# GameBit_Board.net
KiCad netlist of a schematic drawn in EAGLE
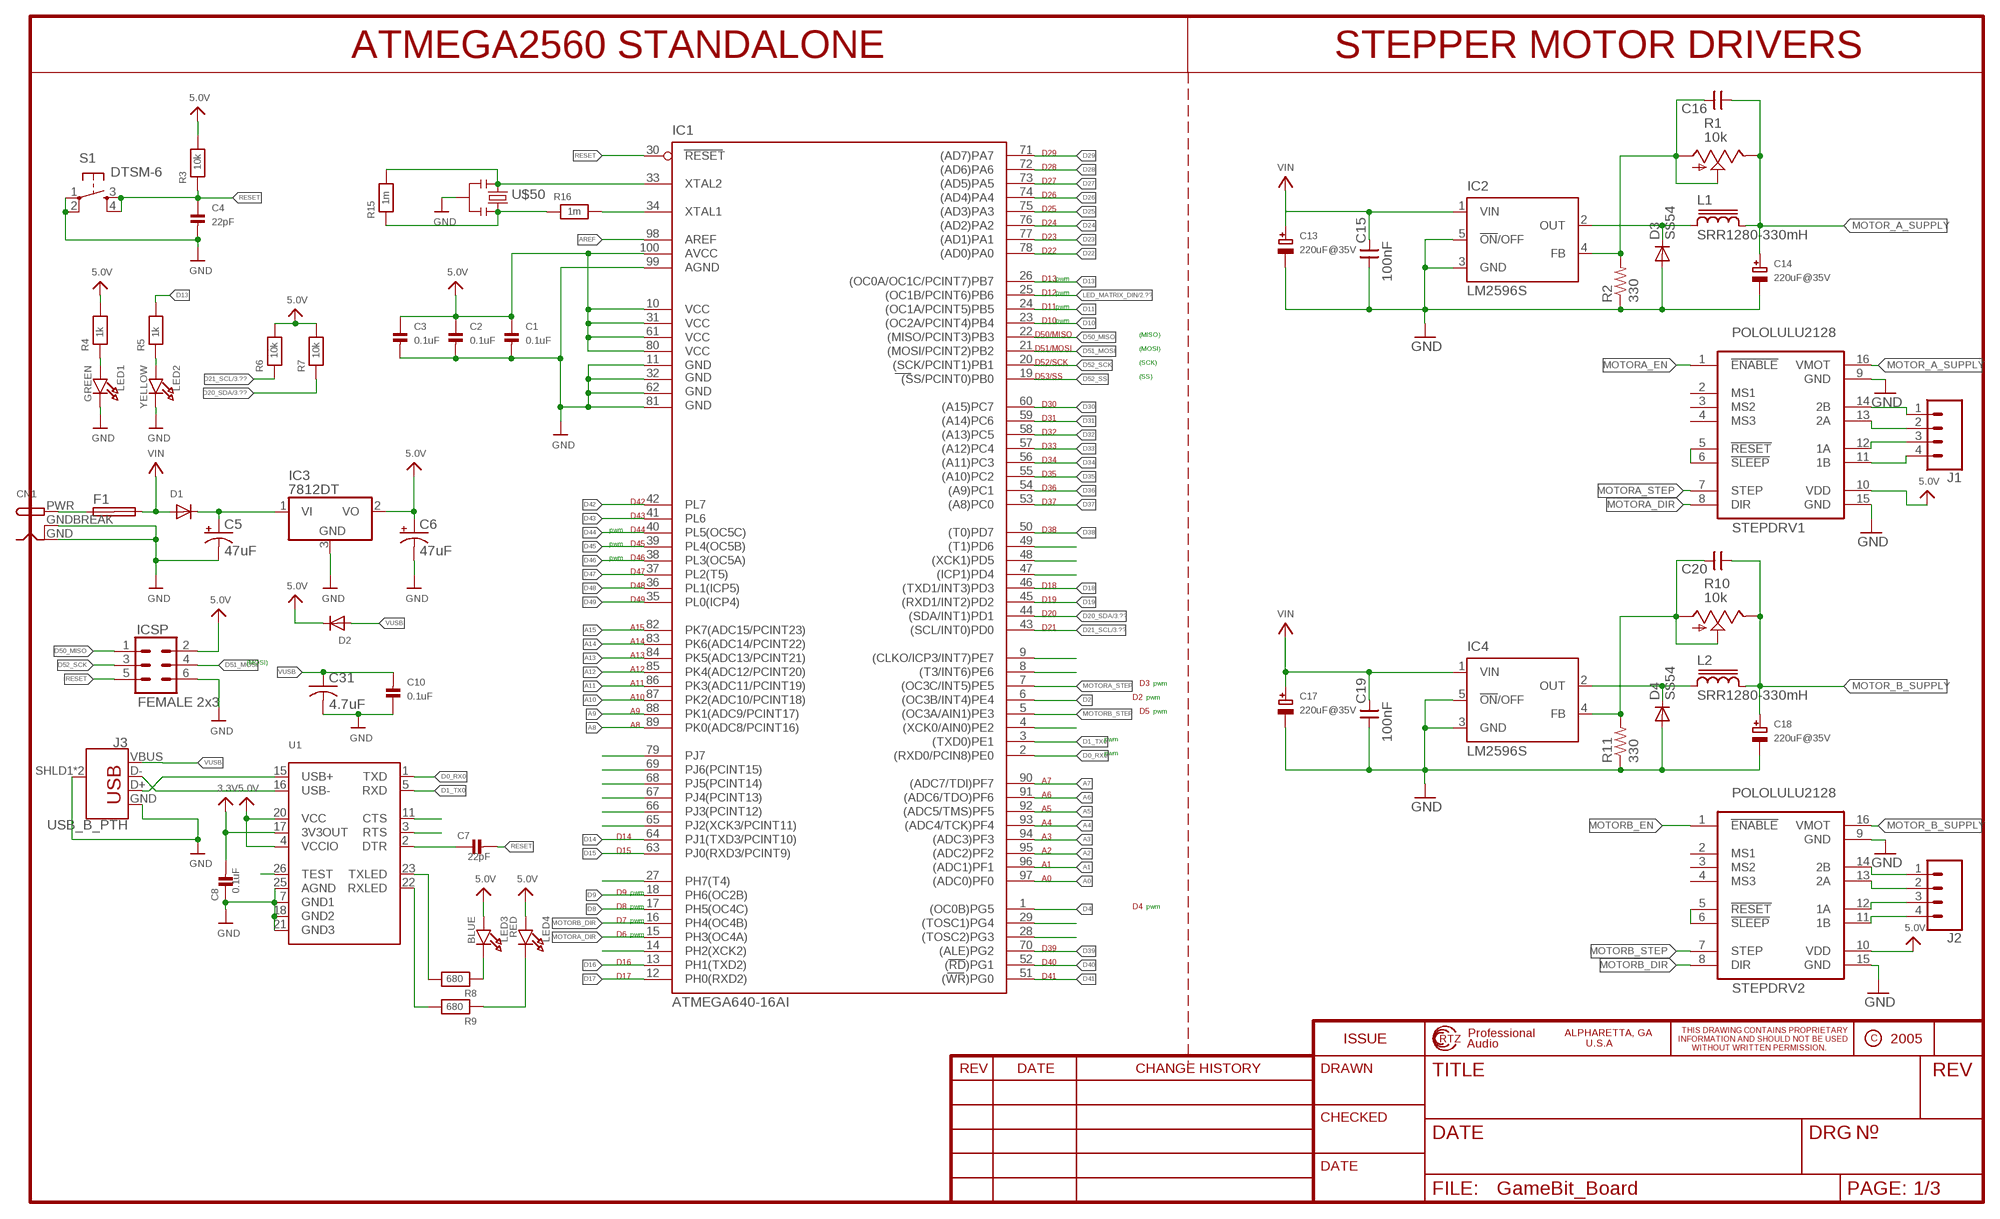
[diagram p0: schematic, sheet 1]
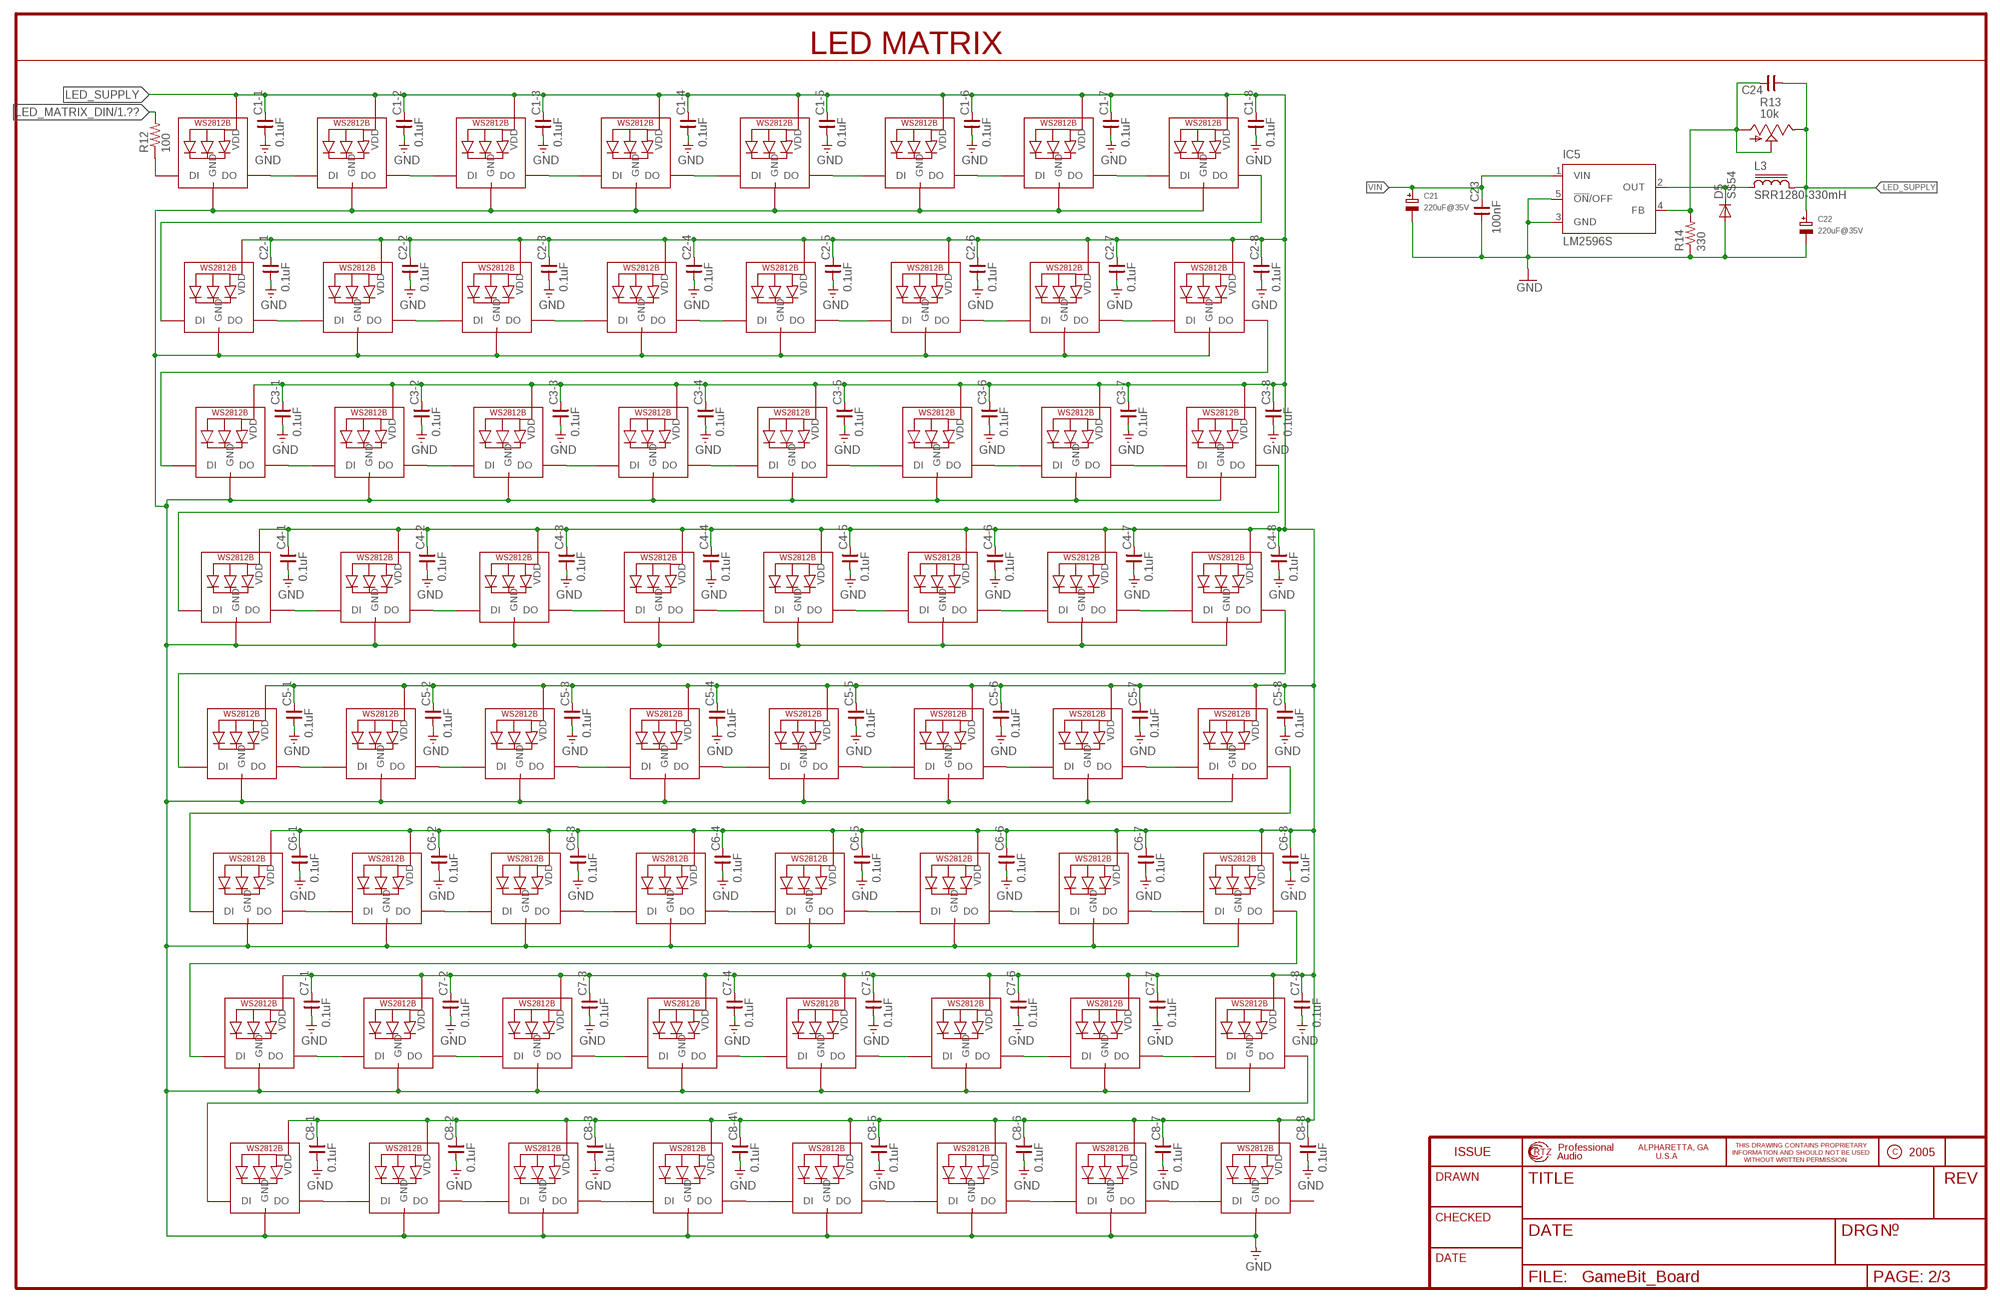
[diagram p1: schematic, sheet 2]
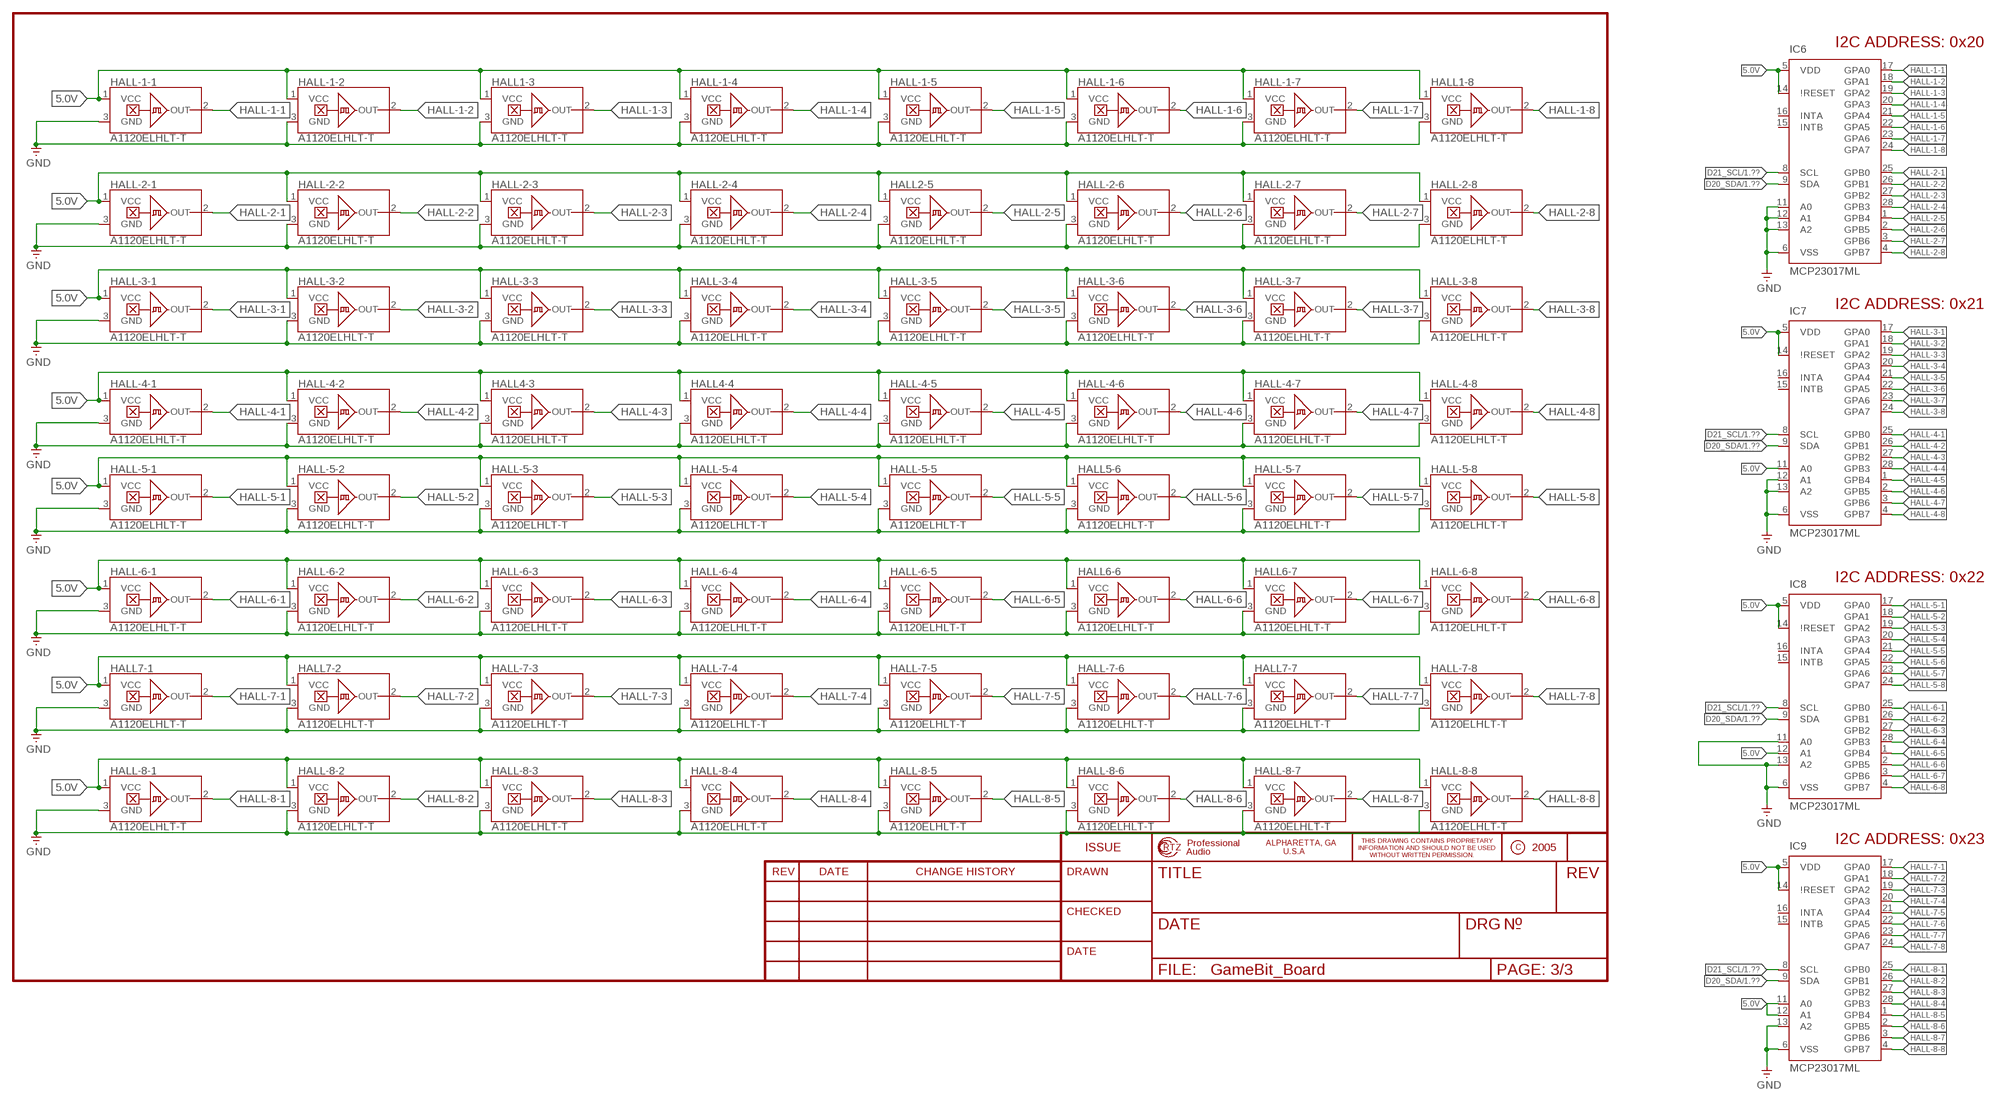
[diagram p2: schematic, sheet 3]

(export (version "E")
  (design (tool "Eeschema 10.0.6"))
  (components
    (comp (ref "C1")
      (value "0.1uF")
      (footprint "eagle-import:0603")
      (libsource (lib "eagle-import") (part "CAP_CERAMIC0603"))
    )
    (comp (ref "C2")
      (value "0.1uF")
      (footprint "eagle-import:0603")
      (libsource (lib "eagle-import") (part "CAP_CERAMIC0603"))
    )
    (comp (ref "C3")
      (value "0.1uF")
      (footprint "eagle-import:0603")
      (libsource (lib "eagle-import") (part "CAP_CERAMIC0603"))
    )
    (comp (ref "C4")
      (value "22pF")
      (footprint "eagle-import:0603")
      (libsource (lib "eagle-import") (part "CAP_CERAMIC0603"))
    )
    (comp (ref "C5")
      (value "47uF")
      (footprint "eagle-import:PANASONIC_D")
      (libsource (lib "eagle-import") (part "CPOL-USD"))
    )
    (comp (ref "C6")
      (value "47uF")
      (footprint "eagle-import:PANASONIC_D")
      (libsource (lib "eagle-import") (part "CPOL-USD"))
    )
    (comp (ref "C7")
      (value "22pF")
      (footprint "eagle-import:0603")
      (libsource (lib "eagle-import") (part "CAP_CERAMIC0603"))
    )
    (comp (ref "C8")
      (value "0.1uF")
      (footprint "eagle-import:0603")
      (libsource (lib "eagle-import") (part "CAP_CERAMIC0603"))
    )
    (comp (ref "C10")
      (value "0.1uF")
      (footprint "eagle-import:0603")
      (libsource (lib "eagle-import") (part "CAP_CERAMIC0603"))
    )
    (comp (ref "C13")
      (value "220uF@35V")
      (footprint "eagle-import:PANASONIC_D")
      (libsource (lib "eagle-import") (part "CAP_ELECTROLYTICPANASONIC_D"))
    )
    (comp (ref "C14")
      (value "220uF@35V")
      (footprint "eagle-import:PANASONIC_D")
      (libsource (lib "eagle-import") (part "CAP_ELECTROLYTICPANASONIC_D"))
    )
    (comp (ref "C15")
      (value "100nF")
      (footprint "eagle-import:0603")
      (libsource (lib "eagle-import") (part "CNP-0603"))
    )
    (comp (ref "C16")
      (value "CNP-0603")
      (footprint "eagle-import:0603")
      (libsource (lib "eagle-import") (part "CNP-0603"))
    )
    (comp (ref "C17")
      (value "220uF@35V")
      (footprint "eagle-import:PANASONIC_D")
      (libsource (lib "eagle-import") (part "CAP_ELECTROLYTICPANASONIC_D"))
    )
    (comp (ref "C18")
      (value "220uF@35V")
      (footprint "eagle-import:PANASONIC_D")
      (libsource (lib "eagle-import") (part "CAP_ELECTROLYTICPANASONIC_D"))
    )
    (comp (ref "C19")
      (value "100nF")
      (footprint "eagle-import:0603")
      (libsource (lib "eagle-import") (part "CNP-0603"))
    )
    (comp (ref "C20")
      (value "CNP-0603")
      (footprint "eagle-import:0603")
      (libsource (lib "eagle-import") (part "CNP-0603"))
    )
    (comp (ref "C31")
      (value "4.7uF")
      (footprint "eagle-import:C0805")
      (libsource (lib "eagle-import") (part "C-USC0805"))
    )
    (comp (ref "CN1")
      (value "DCBARRELPTH")
      (footprint "eagle-import:DCJACK_2MM_PTH")
      (libsource (lib "eagle-import") (part "DCBARRELPTH"))
    )
    (comp (ref "D1")
      (value "DIODESOD-123")
      (footprint "eagle-import:SOD-123")
      (libsource (lib "eagle-import") (part "DIODESOD-123"))
    )
    (comp (ref "D2")
      (value "DIODESOD-123")
      (footprint "eagle-import:SOD-123")
      (libsource (lib "eagle-import") (part "DIODESOD-123"))
    )
    (comp (ref "D3")
      (value "SS54")
      (footprint "eagle-import:DO214AB")
      (fields (field (name "MF") "Fairchild") (field (name "MPN") "S3G"))
      (libsource (lib "eagle-import") (part "S3G"))
    )
    (comp (ref "D4")
      (value "SS54")
      (footprint "eagle-import:DO214AB")
      (fields (field (name "MF") "Fairchild") (field (name "MPN") "S3G"))
      (libsource (lib "eagle-import") (part "S3G"))
    )
    (comp (ref "F1")
      (value "SHK20L")
      (footprint "eagle-import:SHK20L")
      (libsource (lib "eagle-import") (part "SHK20L"))
    )
    (comp (ref "IC1")
      (value "ATMEGA640-16AI")
      (footprint "eagle-import:TQFP100")
      (libsource (lib "eagle-import") (part "ATMEGAAI640-16"))
    )
    (comp (ref "IC2")
      (value "LM2596S")
      (footprint "eagle-import:TO263-5")
      (fields (field (name "MF") "NATIONAL SEMICONDUCTOR") (field (name "MPN") "LM2596S-ADJ/NOPB"))
      (libsource (lib "eagle-import") (part "LM2596S"))
    )
    (comp (ref "IC3")
      (value "7812DT")
      (footprint "eagle-import:TO252")
      (libsource (lib "eagle-import") (part "78DT12"))
    )
    (comp (ref "IC4")
      (value "LM2596S")
      (footprint "eagle-import:TO263-5")
      (fields (field (name "MF") "NATIONAL SEMICONDUCTOR") (field (name "MPN") "LM2596S-ADJ/NOPB"))
      (libsource (lib "eagle-import") (part "LM2596S"))
    )
    (comp (ref "ICSP")
      (value "FEMALE 2x3")
      (footprint "eagle-import:2X3")
      (libsource (lib "eagle-import") (part "CONN_03X2FEMALE"))
    )
    (comp (ref "J1")
      (value "CONN_04JST-PTH-VERT")
      (footprint "eagle-import:JST-4-PTH-VERT")
      (libsource (lib "eagle-import") (part "CONN_04JST-PTH-VERT"))
    )
    (comp (ref "J2")
      (value "CONN_04JST-PTH-VERT")
      (footprint "eagle-import:JST-4-PTH-VERT")
      (libsource (lib "eagle-import") (part "CONN_04JST-PTH-VERT"))
    )
    (comp (ref "J3")
      (value "USB_B_PTH")
      (footprint "eagle-import:USB-B-PTH")
      (libsource (lib "eagle-import") (part "USB_B_PTH"))
    )
    (comp (ref "L1")
      (value "SRR1280-330mH")
      (footprint "eagle-import:SRR1280")
      (libsource (lib "eagle-import") (part "SRR1280"))
    )
    (comp (ref "L2")
      (value "SRR1280-330mH")
      (footprint "eagle-import:SRR1280")
      (libsource (lib "eagle-import") (part "SRR1280"))
    )
    (comp (ref "LED1")
      (value "GREEN")
      (footprint "eagle-import:CHIPLED_0603")
      (libsource (lib "eagle-import") (part "LED0603"))
    )
    (comp (ref "LED2")
      (value "YELLOW")
      (footprint "eagle-import:CHIPLED_0603")
      (libsource (lib "eagle-import") (part "LED0603"))
    )
    (comp (ref "LED3")
      (value "BLUE")
      (footprint "eagle-import:CHIPLED_0603")
      (libsource (lib "eagle-import") (part "LED0603"))
    )
    (comp (ref "LED4")
      (value "RED")
      (footprint "eagle-import:CHIPLED_0603")
      (libsource (lib "eagle-import") (part "LED0603"))
    )
    (comp (ref "R1")
      (value "10k")
      (footprint "eagle-import:S64W")
      (libsource (lib "eagle-import") (part "TRIM_US-S64W"))
    )
    (comp (ref "R2")
      (value "330")
      (footprint "eagle-import:R0603")
      (libsource (lib "eagle-import") (part "R-US_R0603"))
    )
    (comp (ref "R3")
      (value "10k")
      (footprint "eagle-import:0603")
      (libsource (lib "eagle-import") (part "RESISTOR0603"))
    )
    (comp (ref "R4")
      (value "1k")
      (footprint "eagle-import:0603")
      (libsource (lib "eagle-import") (part "RESISTOR0603"))
    )
    (comp (ref "R5")
      (value "1k")
      (footprint "eagle-import:0603")
      (libsource (lib "eagle-import") (part "RESISTOR0603"))
    )
    (comp (ref "R6")
      (value "10k")
      (footprint "eagle-import:0603")
      (libsource (lib "eagle-import") (part "RESISTOR0603"))
    )
    (comp (ref "R7")
      (value "10k")
      (footprint "eagle-import:0603")
      (libsource (lib "eagle-import") (part "RESISTOR0603"))
    )
    (comp (ref "R8")
      (value "680")
      (footprint "eagle-import:0603")
      (libsource (lib "eagle-import") (part "RESISTOR0603"))
    )
    (comp (ref "R9")
      (value "680")
      (footprint "eagle-import:0603")
      (libsource (lib "eagle-import") (part "RESISTOR0603"))
    )
    (comp (ref "R10")
      (value "10k")
      (footprint "eagle-import:S64W")
      (libsource (lib "eagle-import") (part "TRIM_US-S64W"))
    )
    (comp (ref "R11")
      (value "330")
      (footprint "eagle-import:R0603")
      (libsource (lib "eagle-import") (part "R-US_R0603"))
    )
    (comp (ref "R15")
      (value "1m")
      (footprint "eagle-import:0805")
      (libsource (lib "eagle-import") (part "RESISTOR0805"))
    )
    (comp (ref "R16")
      (value "1m")
      (footprint "eagle-import:0805")
      (libsource (lib "eagle-import") (part "RESISTOR0805"))
    )
    (comp (ref "S1")
      (value "DTSM-6")
      (footprint "eagle-import:DTSM-6")
      (libsource (lib "eagle-import") (part "DTSM-6"))
    )
    (comp (ref "STEPDRV1")
      (value "POLOLULU2128")
      (footprint "eagle-import:POLOLULU2128")
      (libsource (lib "eagle-import") (part "POLOLULU2128"))
    )
    (comp (ref "STEPDRV2")
      (value "POLOLULU2128")
      (footprint "eagle-import:POLOLULU2128")
      (libsource (lib "eagle-import") (part "POLOLULU2128"))
    )
    (comp (ref "U$50")
      (value "RESONATORSMD")
      (footprint "eagle-import:RESONATOR-SMD")
      (libsource (lib "eagle-import") (part "RESONATORSMD"))
    )
    (comp (ref "U1")
      (value "FT232RLSSOP28")
      (footprint "eagle-import:SSOP28DB")
      (libsource (lib "eagle-import") (part "FT232RLSSOP28"))
    )
    (comp (ref "C1-1")
      (value "0.1uF")
      (footprint "eagle-import:0805")
      (libsource (lib "eagle-import") (part "CNP-0805"))
    )
    (comp (ref "C1-2")
      (value "0.1uF")
      (footprint "eagle-import:0805")
      (libsource (lib "eagle-import") (part "CNP-0805"))
    )
    (comp (ref "C1-3")
      (value "0.1uF")
      (footprint "eagle-import:0805")
      (libsource (lib "eagle-import") (part "CNP-0805"))
    )
    (comp (ref "C1-4")
      (value "0.1uF")
      (footprint "eagle-import:0805")
      (libsource (lib "eagle-import") (part "CNP-0805"))
    )
    (comp (ref "C1-5")
      (value "0.1uF")
      (footprint "eagle-import:0805")
      (libsource (lib "eagle-import") (part "CNP-0805"))
    )
    (comp (ref "C1-6")
      (value "0.1uF")
      (footprint "eagle-import:0805")
      (libsource (lib "eagle-import") (part "CNP-0805"))
    )
    (comp (ref "C1-7")
      (value "0.1uF")
      (footprint "eagle-import:0805")
      (libsource (lib "eagle-import") (part "CNP-0805"))
    )
    (comp (ref "C1-8")
      (value "0.1uF")
      (footprint "eagle-import:0805")
      (libsource (lib "eagle-import") (part "CNP-0805"))
    )
    (comp (ref "C2-1")
      (value "0.1uF")
      (footprint "eagle-import:0805")
      (libsource (lib "eagle-import") (part "CNP-0805"))
    )
    (comp (ref "C2-2")
      (value "0.1uF")
      (footprint "eagle-import:0805")
      (libsource (lib "eagle-import") (part "CNP-0805"))
    )
    (comp (ref "C2-3")
      (value "0.1uF")
      (footprint "eagle-import:0805")
      (libsource (lib "eagle-import") (part "CNP-0805"))
    )
    (comp (ref "C2-4")
      (value "0.1uF")
      (footprint "eagle-import:0805")
      (libsource (lib "eagle-import") (part "CNP-0805"))
    )
    (comp (ref "C2-5")
      (value "0.1uF")
      (footprint "eagle-import:0805")
      (libsource (lib "eagle-import") (part "CNP-0805"))
    )
    (comp (ref "C2-6")
      (value "0.1uF")
      (footprint "eagle-import:0805")
      (libsource (lib "eagle-import") (part "CNP-0805"))
    )
    (comp (ref "C2-7")
      (value "0.1uF")
      (footprint "eagle-import:0805")
      (libsource (lib "eagle-import") (part "CNP-0805"))
    )
    (comp (ref "C2-8")
      (value "0.1uF")
      (footprint "eagle-import:0805")
      (libsource (lib "eagle-import") (part "CNP-0805"))
    )
    (comp (ref "C3-1")
      (value "0.1uF")
      (footprint "eagle-import:0805")
      (libsource (lib "eagle-import") (part "CNP-0805"))
    )
    (comp (ref "C3-2")
      (value "0.1uF")
      (footprint "eagle-import:0805")
      (libsource (lib "eagle-import") (part "CNP-0805"))
    )
    (comp (ref "C3-3")
      (value "0.1uF")
      (footprint "eagle-import:0805")
      (libsource (lib "eagle-import") (part "CNP-0805"))
    )
    (comp (ref "C3-4")
      (value "0.1uF")
      (footprint "eagle-import:0805")
      (libsource (lib "eagle-import") (part "CNP-0805"))
    )
    (comp (ref "C3-5")
      (value "0.1uF")
      (footprint "eagle-import:0805")
      (libsource (lib "eagle-import") (part "CNP-0805"))
    )
    (comp (ref "C3-6")
      (value "0.1uF")
      (footprint "eagle-import:0805")
      (libsource (lib "eagle-import") (part "CNP-0805"))
    )
    (comp (ref "C3-7")
      (value "0.1uF")
      (footprint "eagle-import:0805")
      (libsource (lib "eagle-import") (part "CNP-0805"))
    )
    (comp (ref "C3-8")
      (value "0.1uF")
      (footprint "eagle-import:0805")
      (libsource (lib "eagle-import") (part "CNP-0805"))
    )
    (comp (ref "C4-1")
      (value "0.1uF")
      (footprint "eagle-import:0805")
      (libsource (lib "eagle-import") (part "CNP-0805"))
    )
    (comp (ref "C4-2")
      (value "0.1uF")
      (footprint "eagle-import:0805")
      (libsource (lib "eagle-import") (part "CNP-0805"))
    )
    (comp (ref "C4-3")
      (value "0.1uF")
      (footprint "eagle-import:0805")
      (libsource (lib "eagle-import") (part "CNP-0805"))
    )
    (comp (ref "C4-4")
      (value "0.1uF")
      (footprint "eagle-import:0805")
      (libsource (lib "eagle-import") (part "CNP-0805"))
    )
    (comp (ref "C4-5")
      (value "0.1uF")
      (footprint "eagle-import:0805")
      (libsource (lib "eagle-import") (part "CNP-0805"))
    )
    (comp (ref "C4-6")
      (value "0.1uF")
      (footprint "eagle-import:0805")
      (libsource (lib "eagle-import") (part "CNP-0805"))
    )
    (comp (ref "C4-7")
      (value "0.1uF")
      (footprint "eagle-import:0805")
      (libsource (lib "eagle-import") (part "CNP-0805"))
    )
    (comp (ref "C4-8")
      (value "0.1uF")
      (footprint "eagle-import:0805")
      (libsource (lib "eagle-import") (part "CNP-0805"))
    )
    (comp (ref "C5-1")
      (value "0.1uF")
      (footprint "eagle-import:0805")
      (libsource (lib "eagle-import") (part "CNP-0805"))
    )
    (comp (ref "C5-2")
      (value "0.1uF")
      (footprint "eagle-import:0805")
      (libsource (lib "eagle-import") (part "CNP-0805"))
    )
    (comp (ref "C5-3")
      (value "0.1uF")
      (footprint "eagle-import:0805")
      (libsource (lib "eagle-import") (part "CNP-0805"))
    )
    (comp (ref "C5-4")
      (value "0.1uF")
      (footprint "eagle-import:0805")
      (libsource (lib "eagle-import") (part "CNP-0805"))
    )
    (comp (ref "C5-5")
      (value "0.1uF")
      (footprint "eagle-import:0805")
      (libsource (lib "eagle-import") (part "CNP-0805"))
    )
    (comp (ref "C5-6")
      (value "0.1uF")
      (footprint "eagle-import:0805")
      (libsource (lib "eagle-import") (part "CNP-0805"))
    )
    (comp (ref "C5-7")
      (value "0.1uF")
      (footprint "eagle-import:0805")
      (libsource (lib "eagle-import") (part "CNP-0805"))
    )
    (comp (ref "C5-8")
      (value "0.1uF")
      (footprint "eagle-import:0805")
      (libsource (lib "eagle-import") (part "CNP-0805"))
    )
    (comp (ref "C6-1")
      (value "0.1uF")
      (footprint "eagle-import:0805")
      (libsource (lib "eagle-import") (part "CNP-0805"))
    )
    (comp (ref "C6-2")
      (value "0.1uF")
      (footprint "eagle-import:0805")
      (libsource (lib "eagle-import") (part "CNP-0805"))
    )
    (comp (ref "C6-3")
      (value "0.1uF")
      (footprint "eagle-import:0805")
      (libsource (lib "eagle-import") (part "CNP-0805"))
    )
    (comp (ref "C6-4")
      (value "0.1uF")
      (footprint "eagle-import:0805")
      (libsource (lib "eagle-import") (part "CNP-0805"))
    )
    (comp (ref "C6-5")
      (value "0.1uF")
      (footprint "eagle-import:0805")
      (libsource (lib "eagle-import") (part "CNP-0805"))
    )
    (comp (ref "C6-6")
      (value "0.1uF")
      (footprint "eagle-import:0805")
      (libsource (lib "eagle-import") (part "CNP-0805"))
    )
    (comp (ref "C6-7")
      (value "0.1uF")
      (footprint "eagle-import:0805")
      (libsource (lib "eagle-import") (part "CNP-0805"))
    )
    (comp (ref "C6-8")
      (value "0.1uF")
      (footprint "eagle-import:0805")
      (libsource (lib "eagle-import") (part "CNP-0805"))
    )
    (comp (ref "C7-1")
      (value "0.1uF")
      (footprint "eagle-import:0805")
      (libsource (lib "eagle-import") (part "CNP-0805"))
    )
    (comp (ref "C7-2")
      (value "0.1uF")
      (footprint "eagle-import:0805")
      (libsource (lib "eagle-import") (part "CNP-0805"))
    )
    (comp (ref "C7-3")
      (value "0.1uF")
      (footprint "eagle-import:0805")
      (libsource (lib "eagle-import") (part "CNP-0805"))
    )
    (comp (ref "C7-4")
      (value "0.1uF")
      (footprint "eagle-import:0805")
      (libsource (lib "eagle-import") (part "CNP-0805"))
    )
    (comp (ref "C7-5")
      (value "0.1uF")
      (footprint "eagle-import:0805")
      (libsource (lib "eagle-import") (part "CNP-0805"))
    )
    (comp (ref "C7-6")
      (value "0.1uF")
      (footprint "eagle-import:0805")
      (libsource (lib "eagle-import") (part "CNP-0805"))
    )
    (comp (ref "C7-7")
      (value "0.1uF")
      (footprint "eagle-import:0805")
      (libsource (lib "eagle-import") (part "CNP-0805"))
    )
    (comp (ref "C7-8")
      (value "0.1uF")
      (footprint "eagle-import:0805")
      (libsource (lib "eagle-import") (part "CNP-0805"))
    )
    (comp (ref "C8-1")
      (value "0.1uF")
      (footprint "eagle-import:0805")
      (libsource (lib "eagle-import") (part "CNP-0805"))
    )
    (comp (ref "C8-2")
      (value "0.1uF")
      (footprint "eagle-import:0805")
      (libsource (lib "eagle-import") (part "CNP-0805"))
    )
    (comp (ref "C8-3")
      (value "0.1uF")
      (footprint "eagle-import:0805")
      (libsource (lib "eagle-import") (part "CNP-0805"))
    )
    (comp (ref "C8-4\\")
      (value "0.1uF")
      (footprint "eagle-import:0805")
      (libsource (lib "eagle-import") (part "CNP-0805"))
    )
    (comp (ref "C8-5")
      (value "0.1uF")
      (footprint "eagle-import:0805")
      (libsource (lib "eagle-import") (part "CNP-0805"))
    )
    (comp (ref "C8-6")
      (value "0.1uF")
      (footprint "eagle-import:0805")
      (libsource (lib "eagle-import") (part "CNP-0805"))
    )
    (comp (ref "C8-7")
      (value "0.1uF")
      (footprint "eagle-import:0805")
      (libsource (lib "eagle-import") (part "CNP-0805"))
    )
    (comp (ref "C8-8")
      (value "0.1uF")
      (footprint "eagle-import:0805")
      (libsource (lib "eagle-import") (part "CNP-0805"))
    )
    (comp (ref "C21")
      (value "220uF@35V")
      (footprint "eagle-import:PANASONIC_D")
      (libsource (lib "eagle-import") (part "CAP_ELECTROLYTICPANASONIC_D"))
    )
    (comp (ref "C22")
      (value "220uF@35V")
      (footprint "eagle-import:PANASONIC_D")
      (libsource (lib "eagle-import") (part "CAP_ELECTROLYTICPANASONIC_D"))
    )
    (comp (ref "C23")
      (value "100nF")
      (footprint "eagle-import:0603")
      (libsource (lib "eagle-import") (part "CNP-0603"))
    )
    (comp (ref "C24")
      (value "CNP-0603")
      (footprint "eagle-import:0603")
      (libsource (lib "eagle-import") (part "CNP-0603"))
    )
    (comp (ref "D5")
      (value "SS54")
      (footprint "eagle-import:DO214AB")
      (fields (field (name "MF") "Fairchild") (field (name "MPN") "S3G"))
      (libsource (lib "eagle-import") (part "S3G"))
    )
    (comp (ref "IC5")
      (value "LM2596S")
      (footprint "eagle-import:TO263-5")
      (fields (field (name "MF") "NATIONAL SEMICONDUCTOR") (field (name "MPN") "LM2596S-ADJ/NOPB"))
      (libsource (lib "eagle-import") (part "LM2596S"))
    )
    (comp (ref "L3")
      (value "SRR1280-330mH")
      (footprint "eagle-import:SRR1280")
      (libsource (lib "eagle-import") (part "SRR1280"))
    )
    (comp (ref "LED1-1")
      (value "WS2812B5050")
      (footprint "eagle-import:WS2812B")
      (libsource (lib "eagle-import") (part "WS2812B5050"))
    )
    (comp (ref "LED1-2")
      (value "WS2812B5050")
      (footprint "eagle-import:WS2812B")
      (libsource (lib "eagle-import") (part "WS2812B5050"))
    )
    (comp (ref "LED1-3")
      (value "WS2812B5050")
      (footprint "eagle-import:WS2812B")
      (libsource (lib "eagle-import") (part "WS2812B5050"))
    )
    (comp (ref "LED1-4")
      (value "WS2812B5050")
      (footprint "eagle-import:WS2812B")
      (libsource (lib "eagle-import") (part "WS2812B5050"))
    )
    (comp (ref "LED1-5")
      (value "WS2812B5050")
      (footprint "eagle-import:WS2812B")
      (libsource (lib "eagle-import") (part "WS2812B5050"))
    )
    (comp (ref "LED1-6")
      (value "WS2812B5050")
      (footprint "eagle-import:WS2812B")
      (libsource (lib "eagle-import") (part "WS2812B5050"))
    )
    (comp (ref "LED1-7")
      (value "WS2812B5050")
      (footprint "eagle-import:WS2812B")
      (libsource (lib "eagle-import") (part "WS2812B5050"))
    )
    (comp (ref "LED1-8")
      (value "WS2812B5050")
      (footprint "eagle-import:WS2812B")
      (libsource (lib "eagle-import") (part "WS2812B5050"))
    )
    (comp (ref "LED2-1")
      (value "WS2812B5050")
      (footprint "eagle-import:WS2812B")
      (libsource (lib "eagle-import") (part "WS2812B5050"))
    )
    (comp (ref "LED2-2")
      (value "WS2812B5050")
      (footprint "eagle-import:WS2812B")
      (libsource (lib "eagle-import") (part "WS2812B5050"))
    )
    (comp (ref "LED2-3")
      (value "WS2812B5050")
      (footprint "eagle-import:WS2812B")
      (libsource (lib "eagle-import") (part "WS2812B5050"))
    )
    (comp (ref "LED2-4")
      (value "WS2812B5050")
      (footprint "eagle-import:WS2812B")
      (libsource (lib "eagle-import") (part "WS2812B5050"))
    )
    (comp (ref "LED2-5")
      (value "WS2812B5050")
      (footprint "eagle-import:WS2812B")
      (libsource (lib "eagle-import") (part "WS2812B5050"))
    )
    (comp (ref "LED2-6")
      (value "WS2812B5050")
      (footprint "eagle-import:WS2812B")
      (libsource (lib "eagle-import") (part "WS2812B5050"))
    )
    (comp (ref "LED2-7")
      (value "WS2812B5050")
      (footprint "eagle-import:WS2812B")
      (libsource (lib "eagle-import") (part "WS2812B5050"))
    )
    (comp (ref "LED2-8")
      (value "WS2812B5050")
      (footprint "eagle-import:WS2812B")
      (libsource (lib "eagle-import") (part "WS2812B5050"))
    )
    (comp (ref "LED3-1")
      (value "WS2812B5050")
      (footprint "eagle-import:WS2812B")
      (libsource (lib "eagle-import") (part "WS2812B5050"))
    )
    (comp (ref "LED3-2")
      (value "WS2812B5050")
      (footprint "eagle-import:WS2812B")
      (libsource (lib "eagle-import") (part "WS2812B5050"))
    )
    (comp (ref "LED3-3")
      (value "WS2812B5050")
      (footprint "eagle-import:WS2812B")
      (libsource (lib "eagle-import") (part "WS2812B5050"))
    )
    (comp (ref "LED3-4")
      (value "WS2812B5050")
      (footprint "eagle-import:WS2812B")
      (libsource (lib "eagle-import") (part "WS2812B5050"))
    )
    (comp (ref "LED3-5")
      (value "WS2812B5050")
      (footprint "eagle-import:WS2812B")
      (libsource (lib "eagle-import") (part "WS2812B5050"))
    )
    (comp (ref "LED3-6")
      (value "WS2812B5050")
      (footprint "eagle-import:WS2812B")
      (libsource (lib "eagle-import") (part "WS2812B5050"))
    )
    (comp (ref "LED3-7")
      (value "WS2812B5050")
      (footprint "eagle-import:WS2812B")
      (libsource (lib "eagle-import") (part "WS2812B5050"))
    )
    (comp (ref "LED3-8")
      (value "WS2812B5050")
      (footprint "eagle-import:WS2812B")
      (libsource (lib "eagle-import") (part "WS2812B5050"))
    )
    (comp (ref "LED4-1")
      (value "WS2812B5050")
      (footprint "eagle-import:WS2812B")
      (libsource (lib "eagle-import") (part "WS2812B5050"))
    )
    (comp (ref "LED4-2")
      (value "WS2812B5050")
      (footprint "eagle-import:WS2812B")
      (libsource (lib "eagle-import") (part "WS2812B5050"))
    )
    (comp (ref "LED4-3")
      (value "WS2812B5050")
      (footprint "eagle-import:WS2812B")
      (libsource (lib "eagle-import") (part "WS2812B5050"))
    )
    (comp (ref "LED4-4")
      (value "WS2812B5050")
      (footprint "eagle-import:WS2812B")
      (libsource (lib "eagle-import") (part "WS2812B5050"))
    )
    (comp (ref "LED4-5")
      (value "WS2812B5050")
      (footprint "eagle-import:WS2812B")
      (libsource (lib "eagle-import") (part "WS2812B5050"))
    )
    (comp (ref "LED4-6")
      (value "WS2812B5050")
      (footprint "eagle-import:WS2812B")
      (libsource (lib "eagle-import") (part "WS2812B5050"))
    )
    (comp (ref "LED4-7")
      (value "WS2812B5050")
      (footprint "eagle-import:WS2812B")
      (libsource (lib "eagle-import") (part "WS2812B5050"))
    )
    (comp (ref "LED4-8")
      (value "WS2812B5050")
      (footprint "eagle-import:WS2812B")
      (libsource (lib "eagle-import") (part "WS2812B5050"))
    )
    (comp (ref "LED5-1")
      (value "WS2812B5050")
      (footprint "eagle-import:WS2812B")
      (libsource (lib "eagle-import") (part "WS2812B5050"))
    )
    (comp (ref "LED5-2")
      (value "WS2812B5050")
      (footprint "eagle-import:WS2812B")
      (libsource (lib "eagle-import") (part "WS2812B5050"))
    )
    (comp (ref "LED5-3")
      (value "WS2812B5050")
      (footprint "eagle-import:WS2812B")
      (libsource (lib "eagle-import") (part "WS2812B5050"))
    )
    (comp (ref "LED5-4")
      (value "WS2812B5050")
      (footprint "eagle-import:WS2812B")
      (libsource (lib "eagle-import") (part "WS2812B5050"))
    )
    (comp (ref "LED5-5")
      (value "WS2812B5050")
      (footprint "eagle-import:WS2812B")
      (libsource (lib "eagle-import") (part "WS2812B5050"))
    )
    (comp (ref "LED5-6")
      (value "WS2812B5050")
      (footprint "eagle-import:WS2812B")
      (libsource (lib "eagle-import") (part "WS2812B5050"))
    )
    (comp (ref "LED5-7")
      (value "WS2812B5050")
      (footprint "eagle-import:WS2812B")
      (libsource (lib "eagle-import") (part "WS2812B5050"))
    )
    (comp (ref "LED5-8")
      (value "WS2812B5050")
      (footprint "eagle-import:WS2812B")
      (libsource (lib "eagle-import") (part "WS2812B5050"))
    )
    (comp (ref "LED6-1")
      (value "WS2812B5050")
      (footprint "eagle-import:WS2812B")
      (libsource (lib "eagle-import") (part "WS2812B5050"))
    )
    (comp (ref "LED6-2")
      (value "WS2812B5050")
      (footprint "eagle-import:WS2812B")
      (libsource (lib "eagle-import") (part "WS2812B5050"))
    )
    (comp (ref "LED6-3")
      (value "WS2812B5050")
      (footprint "eagle-import:WS2812B")
      (libsource (lib "eagle-import") (part "WS2812B5050"))
    )
    (comp (ref "LED6-4")
      (value "WS2812B5050")
      (footprint "eagle-import:WS2812B")
      (libsource (lib "eagle-import") (part "WS2812B5050"))
    )
    (comp (ref "LED6-5")
      (value "WS2812B5050")
      (footprint "eagle-import:WS2812B")
      (libsource (lib "eagle-import") (part "WS2812B5050"))
    )
    (comp (ref "LED6-6")
      (value "WS2812B5050")
      (footprint "eagle-import:WS2812B")
      (libsource (lib "eagle-import") (part "WS2812B5050"))
    )
    (comp (ref "LED6-7")
      (value "WS2812B5050")
      (footprint "eagle-import:WS2812B")
      (libsource (lib "eagle-import") (part "WS2812B5050"))
    )
    (comp (ref "LED6-8")
      (value "WS2812B5050")
      (footprint "eagle-import:WS2812B")
      (libsource (lib "eagle-import") (part "WS2812B5050"))
    )
    (comp (ref "LED7-1")
      (value "WS2812B5050")
      (footprint "eagle-import:WS2812B")
      (libsource (lib "eagle-import") (part "WS2812B5050"))
    )
    (comp (ref "LED7-2")
      (value "WS2812B5050")
      (footprint "eagle-import:WS2812B")
      (libsource (lib "eagle-import") (part "WS2812B5050"))
    )
    (comp (ref "LED7-3")
      (value "WS2812B5050")
      (footprint "eagle-import:WS2812B")
      (libsource (lib "eagle-import") (part "WS2812B5050"))
    )
    (comp (ref "LED7-4")
      (value "WS2812B5050")
      (footprint "eagle-import:WS2812B")
      (libsource (lib "eagle-import") (part "WS2812B5050"))
    )
    (comp (ref "LED7-5")
      (value "WS2812B5050")
      (footprint "eagle-import:WS2812B")
      (libsource (lib "eagle-import") (part "WS2812B5050"))
    )
    (comp (ref "LED7-6")
      (value "WS2812B5050")
      (footprint "eagle-import:WS2812B")
      (libsource (lib "eagle-import") (part "WS2812B5050"))
    )
    (comp (ref "LED7-7")
      (value "WS2812B5050")
      (footprint "eagle-import:WS2812B")
      (libsource (lib "eagle-import") (part "WS2812B5050"))
    )
    (comp (ref "LED7-8")
      (value "WS2812B5050")
      (footprint "eagle-import:WS2812B")
      (libsource (lib "eagle-import") (part "WS2812B5050"))
    )
    (comp (ref "LED8-1")
      (value "WS2812B5050")
      (footprint "eagle-import:WS2812B")
      (libsource (lib "eagle-import") (part "WS2812B5050"))
    )
    (comp (ref "LED8-2")
      (value "WS2812B5050")
      (footprint "eagle-import:WS2812B")
      (libsource (lib "eagle-import") (part "WS2812B5050"))
    )
    (comp (ref "LED8-3")
      (value "WS2812B5050")
      (footprint "eagle-import:WS2812B")
      (libsource (lib "eagle-import") (part "WS2812B5050"))
    )
    (comp (ref "LED8-4")
      (value "WS2812B5050")
      (footprint "eagle-import:WS2812B")
      (libsource (lib "eagle-import") (part "WS2812B5050"))
    )
    (comp (ref "LED8-5")
      (value "WS2812B5050")
      (footprint "eagle-import:WS2812B")
      (libsource (lib "eagle-import") (part "WS2812B5050"))
    )
    (comp (ref "LED8-6")
      (value "WS2812B5050")
      (footprint "eagle-import:WS2812B")
      (libsource (lib "eagle-import") (part "WS2812B5050"))
    )
    (comp (ref "LED8-7")
      (value "WS2812B5050")
      (footprint "eagle-import:WS2812B")
      (libsource (lib "eagle-import") (part "WS2812B5050"))
    )
    (comp (ref "LED8-8")
      (value "WS2812B5050")
      (footprint "eagle-import:WS2812B")
      (libsource (lib "eagle-import") (part "WS2812B5050"))
    )
    (comp (ref "R12")
      (value "100")
      (footprint "eagle-import:R0805")
      (libsource (lib "eagle-import") (part "R-US_R0805"))
    )
    (comp (ref "R13")
      (value "10k")
      (footprint "eagle-import:S64W")
      (libsource (lib "eagle-import") (part "TRIM_US-S64W"))
    )
    (comp (ref "R14")
      (value "330")
      (footprint "eagle-import:R0603")
      (libsource (lib "eagle-import") (part "R-US_R0603"))
    )
    (comp (ref "HALL-1-1")
      (value "A1120ELHLT-T")
      (footprint "eagle-import:SOT95P290X110-3N")
      (libsource (lib "eagle-import") (part "A1120ELHLT-T"))
    )
    (comp (ref "HALL-1-2")
      (value "A1120ELHLT-T")
      (footprint "eagle-import:SOT95P290X110-3N")
      (libsource (lib "eagle-import") (part "A1120ELHLT-T"))
    )
    (comp (ref "HALL-1-4")
      (value "A1120ELHLT-T")
      (footprint "eagle-import:SOT95P290X110-3N")
      (libsource (lib "eagle-import") (part "A1120ELHLT-T"))
    )
    (comp (ref "HALL-1-5")
      (value "A1120ELHLT-T")
      (footprint "eagle-import:SOT95P290X110-3N")
      (libsource (lib "eagle-import") (part "A1120ELHLT-T"))
    )
    (comp (ref "HALL-1-6")
      (value "A1120ELHLT-T")
      (footprint "eagle-import:SOT95P290X110-3N")
      (libsource (lib "eagle-import") (part "A1120ELHLT-T"))
    )
    (comp (ref "HALL-1-7")
      (value "A1120ELHLT-T")
      (footprint "eagle-import:SOT95P290X110-3N")
      (libsource (lib "eagle-import") (part "A1120ELHLT-T"))
    )
    (comp (ref "HALL-2-1")
      (value "A1120ELHLT-T")
      (footprint "eagle-import:SOT95P290X110-3N")
      (libsource (lib "eagle-import") (part "A1120ELHLT-T"))
    )
    (comp (ref "HALL-2-2")
      (value "A1120ELHLT-T")
      (footprint "eagle-import:SOT95P290X110-3N")
      (libsource (lib "eagle-import") (part "A1120ELHLT-T"))
    )
    (comp (ref "HALL-2-3")
      (value "A1120ELHLT-T")
      (footprint "eagle-import:SOT95P290X110-3N")
      (libsource (lib "eagle-import") (part "A1120ELHLT-T"))
    )
    (comp (ref "HALL-2-4")
      (value "A1120ELHLT-T")
      (footprint "eagle-import:SOT95P290X110-3N")
      (libsource (lib "eagle-import") (part "A1120ELHLT-T"))
    )
    (comp (ref "HALL-2-6")
      (value "A1120ELHLT-T")
      (footprint "eagle-import:SOT95P290X110-3N")
      (libsource (lib "eagle-import") (part "A1120ELHLT-T"))
    )
    (comp (ref "HALL-2-7")
      (value "A1120ELHLT-T")
      (footprint "eagle-import:SOT95P290X110-3N")
      (libsource (lib "eagle-import") (part "A1120ELHLT-T"))
    )
    (comp (ref "HALL-2-8")
      (value "A1120ELHLT-T")
      (footprint "eagle-import:SOT95P290X110-3N")
      (libsource (lib "eagle-import") (part "A1120ELHLT-T"))
    )
    (comp (ref "HALL-3-1")
      (value "A1120ELHLT-T")
      (footprint "eagle-import:SOT95P290X110-3N")
      (libsource (lib "eagle-import") (part "A1120ELHLT-T"))
    )
    (comp (ref "HALL-3-2")
      (value "A1120ELHLT-T")
      (footprint "eagle-import:SOT95P290X110-3N")
      (libsource (lib "eagle-import") (part "A1120ELHLT-T"))
    )
    (comp (ref "HALL-3-3")
      (value "A1120ELHLT-T")
      (footprint "eagle-import:SOT95P290X110-3N")
      (libsource (lib "eagle-import") (part "A1120ELHLT-T"))
    )
    (comp (ref "HALL-3-4")
      (value "A1120ELHLT-T")
      (footprint "eagle-import:SOT95P290X110-3N")
      (libsource (lib "eagle-import") (part "A1120ELHLT-T"))
    )
    (comp (ref "HALL-3-5")
      (value "A1120ELHLT-T")
      (footprint "eagle-import:SOT95P290X110-3N")
      (libsource (lib "eagle-import") (part "A1120ELHLT-T"))
    )
    (comp (ref "HALL-3-6")
      (value "A1120ELHLT-T")
      (footprint "eagle-import:SOT95P290X110-3N")
      (libsource (lib "eagle-import") (part "A1120ELHLT-T"))
    )
    (comp (ref "HALL-3-7")
      (value "A1120ELHLT-T")
      (footprint "eagle-import:SOT95P290X110-3N")
      (libsource (lib "eagle-import") (part "A1120ELHLT-T"))
    )
    (comp (ref "HALL-3-8")
      (value "A1120ELHLT-T")
      (footprint "eagle-import:SOT95P290X110-3N")
      (libsource (lib "eagle-import") (part "A1120ELHLT-T"))
    )
    (comp (ref "HALL-4-1")
      (value "A1120ELHLT-T")
      (footprint "eagle-import:SOT95P290X110-3N")
      (libsource (lib "eagle-import") (part "A1120ELHLT-T"))
    )
    (comp (ref "HALL-4-2")
      (value "A1120ELHLT-T")
      (footprint "eagle-import:SOT95P290X110-3N")
      (libsource (lib "eagle-import") (part "A1120ELHLT-T"))
    )
    (comp (ref "HALL-4-5")
      (value "A1120ELHLT-T")
      (footprint "eagle-import:SOT95P290X110-3N")
      (libsource (lib "eagle-import") (part "A1120ELHLT-T"))
    )
    (comp (ref "HALL-4-6")
      (value "A1120ELHLT-T")
      (footprint "eagle-import:SOT95P290X110-3N")
      (libsource (lib "eagle-import") (part "A1120ELHLT-T"))
    )
    (comp (ref "HALL-4-7")
      (value "A1120ELHLT-T")
      (footprint "eagle-import:SOT95P290X110-3N")
      (libsource (lib "eagle-import") (part "A1120ELHLT-T"))
    )
    (comp (ref "HALL-4-8")
      (value "A1120ELHLT-T")
      (footprint "eagle-import:SOT95P290X110-3N")
      (libsource (lib "eagle-import") (part "A1120ELHLT-T"))
    )
    (comp (ref "HALL-5-1")
      (value "A1120ELHLT-T")
      (footprint "eagle-import:SOT95P290X110-3N")
      (libsource (lib "eagle-import") (part "A1120ELHLT-T"))
    )
    (comp (ref "HALL-5-2")
      (value "A1120ELHLT-T")
      (footprint "eagle-import:SOT95P290X110-3N")
      (libsource (lib "eagle-import") (part "A1120ELHLT-T"))
    )
    (comp (ref "HALL-5-3")
      (value "A1120ELHLT-T")
      (footprint "eagle-import:SOT95P290X110-3N")
      (libsource (lib "eagle-import") (part "A1120ELHLT-T"))
    )
    (comp (ref "HALL-5-4")
      (value "A1120ELHLT-T")
      (footprint "eagle-import:SOT95P290X110-3N")
      (libsource (lib "eagle-import") (part "A1120ELHLT-T"))
    )
    (comp (ref "HALL-5-5")
      (value "A1120ELHLT-T")
      (footprint "eagle-import:SOT95P290X110-3N")
      (libsource (lib "eagle-import") (part "A1120ELHLT-T"))
    )
    (comp (ref "HALL-5-7")
      (value "A1120ELHLT-T")
      (footprint "eagle-import:SOT95P290X110-3N")
      (libsource (lib "eagle-import") (part "A1120ELHLT-T"))
    )
    (comp (ref "HALL-5-8")
      (value "A1120ELHLT-T")
      (footprint "eagle-import:SOT95P290X110-3N")
      (libsource (lib "eagle-import") (part "A1120ELHLT-T"))
    )
    (comp (ref "HALL-6-1")
      (value "A1120ELHLT-T")
      (footprint "eagle-import:SOT95P290X110-3N")
      (libsource (lib "eagle-import") (part "A1120ELHLT-T"))
    )
    (comp (ref "HALL-6-2")
      (value "A1120ELHLT-T")
      (footprint "eagle-import:SOT95P290X110-3N")
      (libsource (lib "eagle-import") (part "A1120ELHLT-T"))
    )
    (comp (ref "HALL-6-3")
      (value "A1120ELHLT-T")
      (footprint "eagle-import:SOT95P290X110-3N")
      (libsource (lib "eagle-import") (part "A1120ELHLT-T"))
    )
    (comp (ref "HALL-6-4")
      (value "A1120ELHLT-T")
      (footprint "eagle-import:SOT95P290X110-3N")
      (libsource (lib "eagle-import") (part "A1120ELHLT-T"))
    )
    (comp (ref "HALL-6-5")
      (value "A1120ELHLT-T")
      (footprint "eagle-import:SOT95P290X110-3N")
      (libsource (lib "eagle-import") (part "A1120ELHLT-T"))
    )
    (comp (ref "HALL-6-8")
      (value "A1120ELHLT-T")
      (footprint "eagle-import:SOT95P290X110-3N")
      (libsource (lib "eagle-import") (part "A1120ELHLT-T"))
    )
    (comp (ref "HALL-7-3")
      (value "A1120ELHLT-T")
      (footprint "eagle-import:SOT95P290X110-3N")
      (libsource (lib "eagle-import") (part "A1120ELHLT-T"))
    )
    (comp (ref "HALL-7-4")
      (value "A1120ELHLT-T")
      (footprint "eagle-import:SOT95P290X110-3N")
      (libsource (lib "eagle-import") (part "A1120ELHLT-T"))
    )
    (comp (ref "HALL-7-5")
      (value "A1120ELHLT-T")
      (footprint "eagle-import:SOT95P290X110-3N")
      (libsource (lib "eagle-import") (part "A1120ELHLT-T"))
    )
    (comp (ref "HALL-7-6")
      (value "A1120ELHLT-T")
      (footprint "eagle-import:SOT95P290X110-3N")
      (libsource (lib "eagle-import") (part "A1120ELHLT-T"))
    )
    (comp (ref "HALL-7-8")
      (value "A1120ELHLT-T")
      (footprint "eagle-import:SOT95P290X110-3N")
      (libsource (lib "eagle-import") (part "A1120ELHLT-T"))
    )
    (comp (ref "HALL-8-1")
      (value "A1120ELHLT-T")
      (footprint "eagle-import:SOT95P290X110-3N")
      (libsource (lib "eagle-import") (part "A1120ELHLT-T"))
    )
    (comp (ref "HALL-8-2")
      (value "A1120ELHLT-T")
      (footprint "eagle-import:SOT95P290X110-3N")
      (libsource (lib "eagle-import") (part "A1120ELHLT-T"))
    )
    (comp (ref "HALL-8-3")
      (value "A1120ELHLT-T")
      (footprint "eagle-import:SOT95P290X110-3N")
      (libsource (lib "eagle-import") (part "A1120ELHLT-T"))
    )
    (comp (ref "HALL-8-4")
      (value "A1120ELHLT-T")
      (footprint "eagle-import:SOT95P290X110-3N")
      (libsource (lib "eagle-import") (part "A1120ELHLT-T"))
    )
    (comp (ref "HALL-8-5")
      (value "A1120ELHLT-T")
      (footprint "eagle-import:SOT95P290X110-3N")
      (libsource (lib "eagle-import") (part "A1120ELHLT-T"))
    )
    (comp (ref "HALL-8-6")
      (value "A1120ELHLT-T")
      (footprint "eagle-import:SOT95P290X110-3N")
      (libsource (lib "eagle-import") (part "A1120ELHLT-T"))
    )
    (comp (ref "HALL-8-7")
      (value "A1120ELHLT-T")
      (footprint "eagle-import:SOT95P290X110-3N")
      (libsource (lib "eagle-import") (part "A1120ELHLT-T"))
    )
    (comp (ref "HALL-8-8")
      (value "A1120ELHLT-T")
      (footprint "eagle-import:SOT95P290X110-3N")
      (libsource (lib "eagle-import") (part "A1120ELHLT-T"))
    )
    (comp (ref "HALL1-3")
      (value "A1120ELHLT-T")
      (footprint "eagle-import:SOT95P290X110-3N")
      (libsource (lib "eagle-import") (part "A1120ELHLT-T"))
    )
    (comp (ref "HALL1-8")
      (value "A1120ELHLT-T")
      (footprint "eagle-import:SOT95P290X110-3N")
      (libsource (lib "eagle-import") (part "A1120ELHLT-T"))
    )
    (comp (ref "HALL2-5")
      (value "A1120ELHLT-T")
      (footprint "eagle-import:SOT95P290X110-3N")
      (libsource (lib "eagle-import") (part "A1120ELHLT-T"))
    )
    (comp (ref "HALL4-3")
      (value "A1120ELHLT-T")
      (footprint "eagle-import:SOT95P290X110-3N")
      (libsource (lib "eagle-import") (part "A1120ELHLT-T"))
    )
    (comp (ref "HALL4-4")
      (value "A1120ELHLT-T")
      (footprint "eagle-import:SOT95P290X110-3N")
      (libsource (lib "eagle-import") (part "A1120ELHLT-T"))
    )
    (comp (ref "HALL5-6")
      (value "A1120ELHLT-T")
      (footprint "eagle-import:SOT95P290X110-3N")
      (libsource (lib "eagle-import") (part "A1120ELHLT-T"))
    )
    (comp (ref "HALL6-6")
      (value "A1120ELHLT-T")
      (footprint "eagle-import:SOT95P290X110-3N")
      (libsource (lib "eagle-import") (part "A1120ELHLT-T"))
    )
    (comp (ref "HALL6-7")
      (value "A1120ELHLT-T")
      (footprint "eagle-import:SOT95P290X110-3N")
      (libsource (lib "eagle-import") (part "A1120ELHLT-T"))
    )
    (comp (ref "HALL7-1")
      (value "A1120ELHLT-T")
      (footprint "eagle-import:SOT95P290X110-3N")
      (libsource (lib "eagle-import") (part "A1120ELHLT-T"))
    )
    (comp (ref "HALL7-2")
      (value "A1120ELHLT-T")
      (footprint "eagle-import:SOT95P290X110-3N")
      (libsource (lib "eagle-import") (part "A1120ELHLT-T"))
    )
    (comp (ref "HALL7-7")
      (value "A1120ELHLT-T")
      (footprint "eagle-import:SOT95P290X110-3N")
      (libsource (lib "eagle-import") (part "A1120ELHLT-T"))
    )
    (comp (ref "IC6")
      (value "MCP23017ML")
      (footprint "eagle-import:QFN28-ML_6X6MM")
      (libsource (lib "eagle-import") (part "MCP23017ML"))
    )
    (comp (ref "IC7")
      (value "MCP23017ML")
      (footprint "eagle-import:QFN28-ML_6X6MM")
      (libsource (lib "eagle-import") (part "MCP23017ML"))
    )
    (comp (ref "IC8")
      (value "MCP23017ML")
      (footprint "eagle-import:QFN28-ML_6X6MM")
      (libsource (lib "eagle-import") (part "MCP23017ML"))
    )
    (comp (ref "IC9")
      (value "MCP23017ML")
      (footprint "eagle-import:QFN28-ML_6X6MM")
      (libsource (lib "eagle-import") (part "MCP23017ML"))
    )
  )
  (nets
    (net (code "1") (name "3.3V") (class "Default")
      (node (ref "C8") (pin "2") (pinfunction "P$2_2") (pintype "passive"))
      (node (ref "U1") (pin "17") (pinfunction "3V3OUT_17") (pintype "power_in"))
    )
    (net (code "2") (name "5.0V") (class "Default")
      (node (ref "C1") (pin "1") (pinfunction "P$1_1") (pintype "passive"))
      (node (ref "C2") (pin "1") (pinfunction "P$1_1") (pintype "passive"))
      (node (ref "C3") (pin "1") (pinfunction "P$1_1") (pintype "passive"))
      (node (ref "C6") (pin "+") (pinfunction "+_+") (pintype "passive"))
      (node (ref "D2") (pin "C") (pinfunction "C_C") (pintype "passive"))
      (node (ref "HALL-1-1") (pin "1") (pinfunction "VCC_1") (pintype "bidirectional"))
      (node (ref "HALL-1-2") (pin "1") (pinfunction "VCC_1") (pintype "bidirectional"))
      (node (ref "HALL-1-4") (pin "1") (pinfunction "VCC_1") (pintype "bidirectional"))
      (node (ref "HALL-1-5") (pin "1") (pinfunction "VCC_1") (pintype "bidirectional"))
      (node (ref "HALL-1-6") (pin "1") (pinfunction "VCC_1") (pintype "bidirectional"))
      (node (ref "HALL-1-7") (pin "1") (pinfunction "VCC_1") (pintype "bidirectional"))
      (node (ref "HALL-2-1") (pin "1") (pinfunction "VCC_1") (pintype "bidirectional"))
      (node (ref "HALL-2-2") (pin "1") (pinfunction "VCC_1") (pintype "bidirectional"))
      (node (ref "HALL-2-3") (pin "1") (pinfunction "VCC_1") (pintype "bidirectional"))
      (node (ref "HALL-2-4") (pin "1") (pinfunction "VCC_1") (pintype "bidirectional"))
      (node (ref "HALL-2-6") (pin "1") (pinfunction "VCC_1") (pintype "bidirectional"))
      (node (ref "HALL-2-7") (pin "1") (pinfunction "VCC_1") (pintype "bidirectional"))
      (node (ref "HALL-2-8") (pin "1") (pinfunction "VCC_1") (pintype "bidirectional"))
      (node (ref "HALL-3-1") (pin "1") (pinfunction "VCC_1") (pintype "bidirectional"))
      (node (ref "HALL-3-2") (pin "1") (pinfunction "VCC_1") (pintype "bidirectional"))
      (node (ref "HALL-3-3") (pin "1") (pinfunction "VCC_1") (pintype "bidirectional"))
      (node (ref "HALL-3-4") (pin "1") (pinfunction "VCC_1") (pintype "bidirectional"))
      (node (ref "HALL-3-5") (pin "1") (pinfunction "VCC_1") (pintype "bidirectional"))
      (node (ref "HALL-3-6") (pin "1") (pinfunction "VCC_1") (pintype "bidirectional"))
      (node (ref "HALL-3-7") (pin "1") (pinfunction "VCC_1") (pintype "bidirectional"))
      (node (ref "HALL-3-8") (pin "1") (pinfunction "VCC_1") (pintype "bidirectional"))
      (node (ref "HALL-4-1") (pin "1") (pinfunction "VCC_1") (pintype "bidirectional"))
      (node (ref "HALL-4-2") (pin "1") (pinfunction "VCC_1") (pintype "bidirectional"))
      (node (ref "HALL-4-5") (pin "1") (pinfunction "VCC_1") (pintype "bidirectional"))
      (node (ref "HALL-4-6") (pin "1") (pinfunction "VCC_1") (pintype "bidirectional"))
      (node (ref "HALL-4-7") (pin "1") (pinfunction "VCC_1") (pintype "bidirectional"))
      (node (ref "HALL-4-8") (pin "1") (pinfunction "VCC_1") (pintype "bidirectional"))
      (node (ref "HALL-5-1") (pin "1") (pinfunction "VCC_1") (pintype "bidirectional"))
      (node (ref "HALL-5-2") (pin "1") (pinfunction "VCC_1") (pintype "bidirectional"))
      (node (ref "HALL-5-3") (pin "1") (pinfunction "VCC_1") (pintype "bidirectional"))
      (node (ref "HALL-5-4") (pin "1") (pinfunction "VCC_1") (pintype "bidirectional"))
      (node (ref "HALL-5-5") (pin "1") (pinfunction "VCC_1") (pintype "bidirectional"))
      (node (ref "HALL-5-7") (pin "1") (pinfunction "VCC_1") (pintype "bidirectional"))
      (node (ref "HALL-5-8") (pin "1") (pinfunction "VCC_1") (pintype "bidirectional"))
      (node (ref "HALL-6-1") (pin "1") (pinfunction "VCC_1") (pintype "bidirectional"))
      (node (ref "HALL-6-2") (pin "1") (pinfunction "VCC_1") (pintype "bidirectional"))
      (node (ref "HALL-6-3") (pin "1") (pinfunction "VCC_1") (pintype "bidirectional"))
      (node (ref "HALL-6-4") (pin "1") (pinfunction "VCC_1") (pintype "bidirectional"))
      (node (ref "HALL-6-5") (pin "1") (pinfunction "VCC_1") (pintype "bidirectional"))
      (node (ref "HALL-6-8") (pin "1") (pinfunction "VCC_1") (pintype "bidirectional"))
      (node (ref "HALL-7-3") (pin "1") (pinfunction "VCC_1") (pintype "bidirectional"))
      (node (ref "HALL-7-4") (pin "1") (pinfunction "VCC_1") (pintype "bidirectional"))
      (node (ref "HALL-7-5") (pin "1") (pinfunction "VCC_1") (pintype "bidirectional"))
      (node (ref "HALL-7-6") (pin "1") (pinfunction "VCC_1") (pintype "bidirectional"))
      (node (ref "HALL-7-8") (pin "1") (pinfunction "VCC_1") (pintype "bidirectional"))
      (node (ref "HALL-8-1") (pin "1") (pinfunction "VCC_1") (pintype "bidirectional"))
      (node (ref "HALL-8-2") (pin "1") (pinfunction "VCC_1") (pintype "bidirectional"))
      (node (ref "HALL-8-3") (pin "1") (pinfunction "VCC_1") (pintype "bidirectional"))
      (node (ref "HALL-8-4") (pin "1") (pinfunction "VCC_1") (pintype "bidirectional"))
      (node (ref "HALL-8-5") (pin "1") (pinfunction "VCC_1") (pintype "bidirectional"))
      (node (ref "HALL-8-6") (pin "1") (pinfunction "VCC_1") (pintype "bidirectional"))
      (node (ref "HALL-8-7") (pin "1") (pinfunction "VCC_1") (pintype "bidirectional"))
      (node (ref "HALL-8-8") (pin "1") (pinfunction "VCC_1") (pintype "bidirectional"))
      (node (ref "HALL1-3") (pin "1") (pinfunction "VCC_1") (pintype "bidirectional"))
      (node (ref "HALL1-8") (pin "1") (pinfunction "VCC_1") (pintype "bidirectional"))
      (node (ref "HALL2-5") (pin "1") (pinfunction "VCC_1") (pintype "bidirectional"))
      (node (ref "HALL4-3") (pin "1") (pinfunction "VCC_1") (pintype "bidirectional"))
      (node (ref "HALL4-4") (pin "1") (pinfunction "VCC_1") (pintype "bidirectional"))
      (node (ref "HALL5-6") (pin "1") (pinfunction "VCC_1") (pintype "bidirectional"))
      (node (ref "HALL6-6") (pin "1") (pinfunction "VCC_1") (pintype "bidirectional"))
      (node (ref "HALL6-7") (pin "1") (pinfunction "VCC_1") (pintype "bidirectional"))
      (node (ref "HALL7-1") (pin "1") (pinfunction "VCC_1") (pintype "bidirectional"))
      (node (ref "HALL7-2") (pin "1") (pinfunction "VCC_1") (pintype "bidirectional"))
      (node (ref "HALL7-7") (pin "1") (pinfunction "VCC_1") (pintype "bidirectional"))
      (node (ref "IC1") (pin "10") (pinfunction "VCC_10") (pintype "power_in"))
      (node (ref "IC1") (pin "100") (pinfunction "AVCC_100") (pintype "power_in"))
      (node (ref "IC1") (pin "31") (pinfunction "VCC1_31") (pintype "power_in"))
      (node (ref "IC1") (pin "61") (pinfunction "VCC2_61") (pintype "power_in"))
      (node (ref "IC1") (pin "80") (pinfunction "VCC3_80") (pintype "power_in"))
      (node (ref "IC3") (pin "2") (pinfunction "VO_2") (pintype "passive"))
      (node (ref "IC6") (pin "14") (pinfunction "\\~{RESET}_14") (pintype "input"))
      (node (ref "IC6") (pin "5") (pinfunction "VDD_5") (pintype "power_in"))
      (node (ref "IC7") (pin "11") (pinfunction "A0_11") (pintype "input"))
      (node (ref "IC7") (pin "14") (pinfunction "\\~{RESET}_14") (pintype "input"))
      (node (ref "IC7") (pin "5") (pinfunction "VDD_5") (pintype "power_in"))
      (node (ref "IC8") (pin "12") (pinfunction "A1_12") (pintype "input"))
      (node (ref "IC8") (pin "14") (pinfunction "\\~{RESET}_14") (pintype "input"))
      (node (ref "IC8") (pin "5") (pinfunction "VDD_5") (pintype "power_in"))
      (node (ref "IC9") (pin "11") (pinfunction "A0_11") (pintype "input"))
      (node (ref "IC9") (pin "12") (pinfunction "A1_12") (pintype "input"))
      (node (ref "IC9") (pin "14") (pinfunction "\\~{RESET}_14") (pintype "input"))
      (node (ref "IC9") (pin "5") (pinfunction "VDD_5") (pintype "power_in"))
      (node (ref "ICSP") (pin "2") (pinfunction "2_2") (pintype "bidirectional"))
      (node (ref "LED3") (pin "A") (pinfunction "A_A") (pintype "passive"))
      (node (ref "LED4") (pin "A") (pinfunction "A_A") (pintype "passive"))
      (node (ref "R3") (pin "2") (pinfunction "2_2") (pintype "passive"))
      (node (ref "R4") (pin "2") (pinfunction "2_2") (pintype "passive"))
      (node (ref "R6") (pin "2") (pinfunction "2_2") (pintype "passive"))
      (node (ref "R7") (pin "2") (pinfunction "2_2") (pintype "passive"))
      (node (ref "STEPDRV1") (pin "10") (pinfunction "VDD_10") (pintype "power_in"))
      (node (ref "STEPDRV2") (pin "10") (pinfunction "VDD_10") (pintype "power_in"))
      (node (ref "U1") (pin "20") (pinfunction "VCC_20") (pintype "power_in"))
      (node (ref "U1") (pin "4") (pinfunction "VCCIO_4") (pintype "power_in"))
    )
    (net (code "3") (name "A0") (class "Default")
      (node (ref "IC1") (pin "97") (pinfunction "(ADC0)PF0_97") (pintype "bidirectional"))
    )
    (net (code "4") (name "A1") (class "Default")
      (node (ref "IC1") (pin "96") (pinfunction "(ADC1)PF1_96") (pintype "bidirectional"))
    )
    (net (code "5") (name "A2") (class "Default")
      (node (ref "IC1") (pin "95") (pinfunction "(ADC2)PF2_95") (pintype "bidirectional"))
    )
    (net (code "6") (name "A3") (class "Default")
      (node (ref "IC1") (pin "94") (pinfunction "(ADC3)PF3_94") (pintype "bidirectional"))
    )
    (net (code "7") (name "A4") (class "Default")
      (node (ref "IC1") (pin "93") (pinfunction "(ADC4/TCK)PF4_93") (pintype "bidirectional"))
    )
    (net (code "8") (name "A5") (class "Default")
      (node (ref "IC1") (pin "92") (pinfunction "(ADC5/TMS)PF5_92") (pintype "bidirectional"))
    )
    (net (code "9") (name "A6") (class "Default")
      (node (ref "IC1") (pin "91") (pinfunction "(ADC6/TDO)PF6_91") (pintype "bidirectional"))
    )
    (net (code "10") (name "A7") (class "Default")
      (node (ref "IC1") (pin "90") (pinfunction "(ADC7/TDI)PF7_90") (pintype "bidirectional"))
    )
    (net (code "11") (name "A8") (class "Default")
      (node (ref "IC1") (pin "89") (pinfunction "PK0(ADC8/PCINT16)_89") (pintype "bidirectional"))
    )
    (net (code "12") (name "A9") (class "Default")
      (node (ref "IC1") (pin "88") (pinfunction "PK1(ADC9/PCINT17)_88") (pintype "bidirectional"))
    )
    (net (code "13") (name "A10") (class "Default")
      (node (ref "IC1") (pin "87") (pinfunction "PK2(ADC10/PCINT18)_87") (pintype "bidirectional"))
    )
    (net (code "14") (name "A11") (class "Default")
      (node (ref "IC1") (pin "86") (pinfunction "PK3(ADC11/PCINT19)_86") (pintype "bidirectional"))
    )
    (net (code "15") (name "A12") (class "Default")
      (node (ref "IC1") (pin "85") (pinfunction "PK4(ADC12/PCINT20)_85") (pintype "bidirectional"))
    )
    (net (code "16") (name "A13") (class "Default")
      (node (ref "IC1") (pin "84") (pinfunction "PK5(ADC13/PCINT21)_84") (pintype "bidirectional"))
    )
    (net (code "17") (name "A14") (class "Default")
      (node (ref "IC1") (pin "83") (pinfunction "PK6(ADC14/PCINT22)_83") (pintype "bidirectional"))
    )
    (net (code "18") (name "A15") (class "Default")
      (node (ref "IC1") (pin "82") (pinfunction "PK7(ADC15/PCINT23)_82") (pintype "bidirectional"))
    )
    (net (code "19") (name "AREF") (class "Default")
      (node (ref "IC1") (pin "98") (pinfunction "AREF_98") (pintype "bidirectional"))
    )
    (net (code "20") (name "D0_RX0") (class "Default")
      (node (ref "IC1") (pin "2") (pinfunction "(RXD0/PCIN8)PE0_2") (pintype "bidirectional"))
      (node (ref "U1") (pin "1") (pinfunction "TXD_1") (pintype "output"))
    )
    (net (code "21") (name "D1_TX0") (class "Default")
      (node (ref "IC1") (pin "3") (pinfunction "(TXD0)PE1_3") (pintype "bidirectional"))
      (node (ref "U1") (pin "5") (pinfunction "RXD_5") (pintype "input"))
    )
    (net (code "22") (name "D2") (class "Default")
      (node (ref "IC1") (pin "6") (pinfunction "(OC3B/INT4)PE4_6") (pintype "bidirectional"))
    )
    (net (code "23") (name "D4") (class "Default")
      (node (ref "IC1") (pin "1") (pinfunction "(OC0B)PG5_1") (pintype "bidirectional"))
    )
    (net (code "24") (name "D8") (class "Default")
      (node (ref "IC1") (pin "17") (pinfunction "PH5(OC4C)_17") (pintype "bidirectional"))
    )
    (net (code "25") (name "D9") (class "Default")
      (node (ref "IC1") (pin "18") (pinfunction "PH6(OC2B)_18") (pintype "bidirectional"))
    )
    (net (code "26") (name "D10") (class "Default")
      (node (ref "IC1") (pin "23") (pinfunction "(OC2A/PCINT4)PB4_23") (pintype "bidirectional"))
    )
    (net (code "27") (name "D11") (class "Default")
      (node (ref "IC1") (pin "24") (pinfunction "(OC1A/PCINT5)PB5_24") (pintype "bidirectional"))
    )
    (net (code "28") (name "D13") (class "Default")
      (node (ref "IC1") (pin "26") (pinfunction "(OC0A/OC1C/PCINT7)PB7_26") (pintype "bidirectional"))
      (node (ref "R5") (pin "2") (pinfunction "2_2") (pintype "passive"))
    )
    (net (code "29") (name "D14") (class "Default")
      (node (ref "IC1") (pin "64") (pinfunction "PJ1(TXD3/PCINT10)_64") (pintype "bidirectional"))
    )
    (net (code "30") (name "D15") (class "Default")
      (node (ref "IC1") (pin "63") (pinfunction "PJ0(RXD3/PCINT9)_63") (pintype "bidirectional"))
    )
    (net (code "31") (name "D16") (class "Default")
      (node (ref "IC1") (pin "13") (pinfunction "PH1(TXD2)_13") (pintype "bidirectional"))
    )
    (net (code "32") (name "D17") (class "Default")
      (node (ref "IC1") (pin "12") (pinfunction "PH0(RXD2)_12") (pintype "bidirectional"))
    )
    (net (code "33") (name "D18") (class "Default")
      (node (ref "IC1") (pin "46") (pinfunction "(TXD1/INT3)PD3_46") (pintype "bidirectional"))
    )
    (net (code "34") (name "D19") (class "Default")
      (node (ref "IC1") (pin "45") (pinfunction "(RXD1/INT2)PD2_45") (pintype "bidirectional"))
    )
    (net (code "35") (name "D20_SDA") (class "Default")
      (node (ref "IC1") (pin "44") (pinfunction "(SDA/INT1)PD1_44") (pintype "bidirectional"))
      (node (ref "IC6") (pin "9") (pinfunction "SDA_9") (pintype "bidirectional"))
      (node (ref "IC7") (pin "9") (pinfunction "SDA_9") (pintype "bidirectional"))
      (node (ref "IC8") (pin "9") (pinfunction "SDA_9") (pintype "bidirectional"))
      (node (ref "IC9") (pin "9") (pinfunction "SDA_9") (pintype "bidirectional"))
      (node (ref "R7") (pin "1") (pinfunction "1_1") (pintype "passive"))
    )
    (net (code "36") (name "D21_SCL") (class "Default")
      (node (ref "IC1") (pin "43") (pinfunction "(SCL/INT0)PD0_43") (pintype "bidirectional"))
      (node (ref "IC6") (pin "8") (pinfunction "SCL_8") (pintype "input"))
      (node (ref "IC7") (pin "8") (pinfunction "SCL_8") (pintype "input"))
      (node (ref "IC8") (pin "8") (pinfunction "SCL_8") (pintype "input"))
      (node (ref "IC9") (pin "8") (pinfunction "SCL_8") (pintype "input"))
      (node (ref "R6") (pin "1") (pinfunction "1_1") (pintype "passive"))
    )
    (net (code "37") (name "D22") (class "Default")
      (node (ref "IC1") (pin "78") (pinfunction "(AD0)PA0_78") (pintype "bidirectional"))
    )
    (net (code "38") (name "D23") (class "Default")
      (node (ref "IC1") (pin "77") (pinfunction "(AD1)PA1_77") (pintype "bidirectional"))
    )
    (net (code "39") (name "D24") (class "Default")
      (node (ref "IC1") (pin "76") (pinfunction "(AD2)PA2_76") (pintype "bidirectional"))
    )
    (net (code "40") (name "D25") (class "Default")
      (node (ref "IC1") (pin "75") (pinfunction "(AD3)PA3_75") (pintype "bidirectional"))
    )
    (net (code "41") (name "D26") (class "Default")
      (node (ref "IC1") (pin "74") (pinfunction "(AD4)PA4_74") (pintype "bidirectional"))
    )
    (net (code "42") (name "D27") (class "Default")
      (node (ref "IC1") (pin "73") (pinfunction "(AD5)PA5_73") (pintype "bidirectional"))
    )
    (net (code "43") (name "D28") (class "Default")
      (node (ref "IC1") (pin "72") (pinfunction "(AD6)PA6_72") (pintype "bidirectional"))
    )
    (net (code "44") (name "D29") (class "Default")
      (node (ref "IC1") (pin "71") (pinfunction "(AD7)PA7_71") (pintype "bidirectional"))
    )
    (net (code "45") (name "D30") (class "Default")
      (node (ref "IC1") (pin "60") (pinfunction "(A15)PC7_60") (pintype "bidirectional"))
    )
    (net (code "46") (name "D31") (class "Default")
      (node (ref "IC1") (pin "59") (pinfunction "(A14)PC6_59") (pintype "bidirectional"))
    )
    (net (code "47") (name "D32") (class "Default")
      (node (ref "IC1") (pin "58") (pinfunction "(A13)PC5_58") (pintype "bidirectional"))
    )
    (net (code "48") (name "D33") (class "Default")
      (node (ref "IC1") (pin "57") (pinfunction "(A12)PC4_57") (pintype "bidirectional"))
    )
    (net (code "49") (name "D34") (class "Default")
      (node (ref "IC1") (pin "56") (pinfunction "(A11)PC3_56") (pintype "bidirectional"))
    )
    (net (code "50") (name "D35") (class "Default")
      (node (ref "IC1") (pin "55") (pinfunction "(A10)PC2_55") (pintype "bidirectional"))
    )
    (net (code "51") (name "D36") (class "Default")
      (node (ref "IC1") (pin "54") (pinfunction "(A9)PC1_54") (pintype "bidirectional"))
    )
    (net (code "52") (name "D37") (class "Default")
      (node (ref "IC1") (pin "53") (pinfunction "(A8)PC0_53") (pintype "bidirectional"))
    )
    (net (code "53") (name "D38") (class "Default")
      (node (ref "IC1") (pin "50") (pinfunction "(T0)PD7_50") (pintype "bidirectional"))
    )
    (net (code "54") (name "D39") (class "Default")
      (node (ref "IC1") (pin "70") (pinfunction "(ALE)PG2_70") (pintype "bidirectional"))
    )
    (net (code "55") (name "D40") (class "Default")
      (node (ref "IC1") (pin "52") (pinfunction "(RD)PG1_52") (pintype "bidirectional"))
    )
    (net (code "56") (name "D41") (class "Default")
      (node (ref "IC1") (pin "51") (pinfunction "(WR)PG0_51") (pintype "bidirectional"))
    )
    (net (code "57") (name "D42") (class "Default")
      (node (ref "IC1") (pin "42") (pinfunction "PL7_42") (pintype "bidirectional"))
    )
    (net (code "58") (name "D43") (class "Default")
      (node (ref "IC1") (pin "41") (pinfunction "PL6_41") (pintype "bidirectional"))
    )
    (net (code "59") (name "D44") (class "Default")
      (node (ref "IC1") (pin "40") (pinfunction "PL5(OC5C)_40") (pintype "bidirectional"))
    )
    (net (code "60") (name "D45") (class "Default")
      (node (ref "IC1") (pin "39") (pinfunction "PL4(OC5B)_39") (pintype "bidirectional"))
    )
    (net (code "61") (name "D46") (class "Default")
      (node (ref "IC1") (pin "38") (pinfunction "PL3(OC5A)_38") (pintype "bidirectional"))
    )
    (net (code "62") (name "D47") (class "Default")
      (node (ref "IC1") (pin "37") (pinfunction "PL2(T5)_37") (pintype "bidirectional"))
    )
    (net (code "63") (name "D48") (class "Default")
      (node (ref "IC1") (pin "36") (pinfunction "PL1(ICP5)_36") (pintype "bidirectional"))
    )
    (net (code "64") (name "D49") (class "Default")
      (node (ref "IC1") (pin "35") (pinfunction "PL0(ICP4)_35") (pintype "bidirectional"))
    )
    (net (code "65") (name "D50_MISO") (class "Default")
      (node (ref "IC1") (pin "22") (pinfunction "(MISO/PCINT3)PB3_22") (pintype "bidirectional"))
      (node (ref "ICSP") (pin "1") (pinfunction "1_1") (pintype "bidirectional"))
    )
    (net (code "66") (name "D51_MOSI") (class "Default")
      (node (ref "IC1") (pin "21") (pinfunction "(MOSI/PCINT2)PB2_21") (pintype "bidirectional"))
      (node (ref "ICSP") (pin "4") (pinfunction "4_4") (pintype "bidirectional"))
    )
    (net (code "67") (name "D52_SCK") (class "Default")
      (node (ref "IC1") (pin "20") (pinfunction "(SCK/PCINT1)PB1_20") (pintype "bidirectional"))
      (node (ref "ICSP") (pin "3") (pinfunction "3_3") (pintype "bidirectional"))
    )
    (net (code "68") (name "D52_SS") (class "Default")
      (node (ref "IC1") (pin "19") (pinfunction "(SS/PCINT0)PB0_19") (pintype "bidirectional"))
    )
    (net (code "69") (name "GND") (class "Default")
      (node (ref "C1") (pin "2") (pinfunction "P$2_2") (pintype "passive"))
      (node (ref "C1-1") (pin "1") (pinfunction "1_1") (pintype "passive"))
      (node (ref "C1-2") (pin "1") (pinfunction "1_1") (pintype "passive"))
      (node (ref "C1-3") (pin "1") (pinfunction "1_1") (pintype "passive"))
      (node (ref "C1-4") (pin "1") (pinfunction "1_1") (pintype "passive"))
      (node (ref "C1-5") (pin "1") (pinfunction "1_1") (pintype "passive"))
      (node (ref "C1-6") (pin "1") (pinfunction "1_1") (pintype "passive"))
      (node (ref "C1-7") (pin "1") (pinfunction "1_1") (pintype "passive"))
      (node (ref "C1-8") (pin "1") (pinfunction "1_1") (pintype "passive"))
      (node (ref "C10") (pin "1") (pinfunction "P$1_1") (pintype "passive"))
      (node (ref "C13") (pin "-") (pinfunction "-_-") (pintype "passive"))
      (node (ref "C14") (pin "-") (pinfunction "-_-") (pintype "passive"))
      (node (ref "C15") (pin "1") (pinfunction "1_1") (pintype "passive"))
      (node (ref "C17") (pin "-") (pinfunction "-_-") (pintype "passive"))
      (node (ref "C18") (pin "-") (pinfunction "-_-") (pintype "passive"))
      (node (ref "C19") (pin "1") (pinfunction "1_1") (pintype "passive"))
      (node (ref "C2") (pin "2") (pinfunction "P$2_2") (pintype "passive"))
      (node (ref "C2-1") (pin "1") (pinfunction "1_1") (pintype "passive"))
      (node (ref "C2-2") (pin "1") (pinfunction "1_1") (pintype "passive"))
      (node (ref "C2-3") (pin "1") (pinfunction "1_1") (pintype "passive"))
      (node (ref "C2-4") (pin "1") (pinfunction "1_1") (pintype "passive"))
      (node (ref "C2-5") (pin "1") (pinfunction "1_1") (pintype "passive"))
      (node (ref "C2-6") (pin "1") (pinfunction "1_1") (pintype "passive"))
      (node (ref "C2-7") (pin "1") (pinfunction "1_1") (pintype "passive"))
      (node (ref "C2-8") (pin "1") (pinfunction "1_1") (pintype "passive"))
      (node (ref "C21") (pin "-") (pinfunction "-_-") (pintype "passive"))
      (node (ref "C22") (pin "-") (pinfunction "-_-") (pintype "passive"))
      (node (ref "C23") (pin "1") (pinfunction "1_1") (pintype "passive"))
      (node (ref "C3") (pin "2") (pinfunction "P$2_2") (pintype "passive"))
      (node (ref "C3-1") (pin "1") (pinfunction "1_1") (pintype "passive"))
      (node (ref "C3-2") (pin "1") (pinfunction "1_1") (pintype "passive"))
      (node (ref "C3-3") (pin "1") (pinfunction "1_1") (pintype "passive"))
      (node (ref "C3-4") (pin "1") (pinfunction "1_1") (pintype "passive"))
      (node (ref "C3-5") (pin "1") (pinfunction "1_1") (pintype "passive"))
      (node (ref "C3-6") (pin "1") (pinfunction "1_1") (pintype "passive"))
      (node (ref "C3-7") (pin "1") (pinfunction "1_1") (pintype "passive"))
      (node (ref "C3-8") (pin "1") (pinfunction "1_1") (pintype "passive"))
      (node (ref "C31") (pin "2") (pinfunction "2_2") (pintype "passive"))
      (node (ref "C4") (pin "2") (pinfunction "P$2_2") (pintype "passive"))
      (node (ref "C4-1") (pin "1") (pinfunction "1_1") (pintype "passive"))
      (node (ref "C4-2") (pin "1") (pinfunction "1_1") (pintype "passive"))
      (node (ref "C4-3") (pin "1") (pinfunction "1_1") (pintype "passive"))
      (node (ref "C4-4") (pin "1") (pinfunction "1_1") (pintype "passive"))
      (node (ref "C4-5") (pin "1") (pinfunction "1_1") (pintype "passive"))
      (node (ref "C4-6") (pin "1") (pinfunction "1_1") (pintype "passive"))
      (node (ref "C4-7") (pin "1") (pinfunction "1_1") (pintype "passive"))
      (node (ref "C4-8") (pin "1") (pinfunction "1_1") (pintype "passive"))
      (node (ref "C5") (pin "-") (pinfunction "-_-") (pintype "passive"))
      (node (ref "C5-1") (pin "1") (pinfunction "1_1") (pintype "passive"))
      (node (ref "C5-2") (pin "1") (pinfunction "1_1") (pintype "passive"))
      (node (ref "C5-3") (pin "1") (pinfunction "1_1") (pintype "passive"))
      (node (ref "C5-4") (pin "1") (pinfunction "1_1") (pintype "passive"))
      (node (ref "C5-5") (pin "1") (pinfunction "1_1") (pintype "passive"))
      (node (ref "C5-6") (pin "1") (pinfunction "1_1") (pintype "passive"))
      (node (ref "C5-7") (pin "1") (pinfunction "1_1") (pintype "passive"))
      (node (ref "C5-8") (pin "1") (pinfunction "1_1") (pintype "passive"))
      (node (ref "C6") (pin "-") (pinfunction "-_-") (pintype "passive"))
      (node (ref "C6-1") (pin "1") (pinfunction "1_1") (pintype "passive"))
      (node (ref "C6-2") (pin "1") (pinfunction "1_1") (pintype "passive"))
      (node (ref "C6-3") (pin "1") (pinfunction "1_1") (pintype "passive"))
      (node (ref "C6-4") (pin "1") (pinfunction "1_1") (pintype "passive"))
      (node (ref "C6-5") (pin "1") (pinfunction "1_1") (pintype "passive"))
      (node (ref "C6-6") (pin "1") (pinfunction "1_1") (pintype "passive"))
      (node (ref "C6-7") (pin "1") (pinfunction "1_1") (pintype "passive"))
      (node (ref "C6-8") (pin "1") (pinfunction "1_1") (pintype "passive"))
      (node (ref "C7-1") (pin "1") (pinfunction "1_1") (pintype "passive"))
      (node (ref "C7-2") (pin "1") (pinfunction "1_1") (pintype "passive"))
      (node (ref "C7-3") (pin "1") (pinfunction "1_1") (pintype "passive"))
      (node (ref "C7-4") (pin "1") (pinfunction "1_1") (pintype "passive"))
      (node (ref "C7-5") (pin "1") (pinfunction "1_1") (pintype "passive"))
      (node (ref "C7-6") (pin "1") (pinfunction "1_1") (pintype "passive"))
      (node (ref "C7-7") (pin "1") (pinfunction "1_1") (pintype "passive"))
      (node (ref "C7-8") (pin "1") (pinfunction "1_1") (pintype "passive"))
      (node (ref "C8") (pin "1") (pinfunction "P$1_1") (pintype "passive"))
      (node (ref "C8-1") (pin "1") (pinfunction "1_1") (pintype "passive"))
      (node (ref "C8-2") (pin "1") (pinfunction "1_1") (pintype "passive"))
      (node (ref "C8-3") (pin "1") (pinfunction "1_1") (pintype "passive"))
      (node (ref "C8-4\\") (pin "1") (pinfunction "1_1") (pintype "passive"))
      (node (ref "C8-5") (pin "1") (pinfunction "1_1") (pintype "passive"))
      (node (ref "C8-6") (pin "1") (pinfunction "1_1") (pintype "passive"))
      (node (ref "C8-7") (pin "1") (pinfunction "1_1") (pintype "passive"))
      (node (ref "C8-8") (pin "1") (pinfunction "1_1") (pintype "passive"))
      (node (ref "CN1") (pin "GND") (pinfunction "GND_GND") (pintype "power_in"))
      (node (ref "CN1") (pin "GNDBREAK") (pinfunction "GNDBREAK_GNDBREAK") (pintype "power_in"))
      (node (ref "D3") (pin "A") (pinfunction "A_A") (pintype "passive"))
      (node (ref "D4") (pin "A") (pinfunction "A_A") (pintype "passive"))
      (node (ref "D5") (pin "A") (pinfunction "A_A") (pintype "passive"))
      (node (ref "HALL-1-1") (pin "3") (pinfunction "GND_3") (pintype "bidirectional"))
      (node (ref "HALL-1-2") (pin "3") (pinfunction "GND_3") (pintype "bidirectional"))
      (node (ref "HALL-1-4") (pin "3") (pinfunction "GND_3") (pintype "bidirectional"))
      (node (ref "HALL-1-5") (pin "3") (pinfunction "GND_3") (pintype "bidirectional"))
      (node (ref "HALL-1-6") (pin "3") (pinfunction "GND_3") (pintype "bidirectional"))
      (node (ref "HALL-1-7") (pin "3") (pinfunction "GND_3") (pintype "bidirectional"))
      (node (ref "HALL-2-1") (pin "3") (pinfunction "GND_3") (pintype "bidirectional"))
      (node (ref "HALL-2-2") (pin "3") (pinfunction "GND_3") (pintype "bidirectional"))
      (node (ref "HALL-2-3") (pin "3") (pinfunction "GND_3") (pintype "bidirectional"))
      (node (ref "HALL-2-4") (pin "3") (pinfunction "GND_3") (pintype "bidirectional"))
      (node (ref "HALL-2-6") (pin "3") (pinfunction "GND_3") (pintype "bidirectional"))
      (node (ref "HALL-2-7") (pin "3") (pinfunction "GND_3") (pintype "bidirectional"))
      (node (ref "HALL-2-8") (pin "3") (pinfunction "GND_3") (pintype "bidirectional"))
      (node (ref "HALL-3-1") (pin "3") (pinfunction "GND_3") (pintype "bidirectional"))
      (node (ref "HALL-3-2") (pin "3") (pinfunction "GND_3") (pintype "bidirectional"))
      (node (ref "HALL-3-3") (pin "3") (pinfunction "GND_3") (pintype "bidirectional"))
      (node (ref "HALL-3-4") (pin "3") (pinfunction "GND_3") (pintype "bidirectional"))
      (node (ref "HALL-3-5") (pin "3") (pinfunction "GND_3") (pintype "bidirectional"))
      (node (ref "HALL-3-6") (pin "3") (pinfunction "GND_3") (pintype "bidirectional"))
      (node (ref "HALL-3-7") (pin "3") (pinfunction "GND_3") (pintype "bidirectional"))
      (node (ref "HALL-3-8") (pin "3") (pinfunction "GND_3") (pintype "bidirectional"))
      (node (ref "HALL-4-1") (pin "3") (pinfunction "GND_3") (pintype "bidirectional"))
      (node (ref "HALL-4-2") (pin "3") (pinfunction "GND_3") (pintype "bidirectional"))
      (node (ref "HALL-4-5") (pin "3") (pinfunction "GND_3") (pintype "bidirectional"))
      (node (ref "HALL-4-6") (pin "3") (pinfunction "GND_3") (pintype "bidirectional"))
      (node (ref "HALL-4-7") (pin "3") (pinfunction "GND_3") (pintype "bidirectional"))
      (node (ref "HALL-4-8") (pin "3") (pinfunction "GND_3") (pintype "bidirectional"))
      (node (ref "HALL-5-1") (pin "3") (pinfunction "GND_3") (pintype "bidirectional"))
      (node (ref "HALL-5-2") (pin "3") (pinfunction "GND_3") (pintype "bidirectional"))
      (node (ref "HALL-5-3") (pin "3") (pinfunction "GND_3") (pintype "bidirectional"))
      (node (ref "HALL-5-4") (pin "3") (pinfunction "GND_3") (pintype "bidirectional"))
      (node (ref "HALL-5-5") (pin "3") (pinfunction "GND_3") (pintype "bidirectional"))
      (node (ref "HALL-5-7") (pin "3") (pinfunction "GND_3") (pintype "bidirectional"))
      (node (ref "HALL-5-8") (pin "3") (pinfunction "GND_3") (pintype "bidirectional"))
      (node (ref "HALL-6-1") (pin "3") (pinfunction "GND_3") (pintype "bidirectional"))
      (node (ref "HALL-6-2") (pin "3") (pinfunction "GND_3") (pintype "bidirectional"))
      (node (ref "HALL-6-3") (pin "3") (pinfunction "GND_3") (pintype "bidirectional"))
      (node (ref "HALL-6-4") (pin "3") (pinfunction "GND_3") (pintype "bidirectional"))
      (node (ref "HALL-6-5") (pin "3") (pinfunction "GND_3") (pintype "bidirectional"))
      (node (ref "HALL-6-8") (pin "3") (pinfunction "GND_3") (pintype "bidirectional"))
      (node (ref "HALL-7-3") (pin "3") (pinfunction "GND_3") (pintype "bidirectional"))
      (node (ref "HALL-7-4") (pin "3") (pinfunction "GND_3") (pintype "bidirectional"))
      (node (ref "HALL-7-5") (pin "3") (pinfunction "GND_3") (pintype "bidirectional"))
      (node (ref "HALL-7-6") (pin "3") (pinfunction "GND_3") (pintype "bidirectional"))
      (node (ref "HALL-7-8") (pin "3") (pinfunction "GND_3") (pintype "bidirectional"))
      (node (ref "HALL-8-1") (pin "3") (pinfunction "GND_3") (pintype "bidirectional"))
      (node (ref "HALL-8-2") (pin "3") (pinfunction "GND_3") (pintype "bidirectional"))
      (node (ref "HALL-8-3") (pin "3") (pinfunction "GND_3") (pintype "bidirectional"))
      (node (ref "HALL-8-4") (pin "3") (pinfunction "GND_3") (pintype "bidirectional"))
      (node (ref "HALL-8-5") (pin "3") (pinfunction "GND_3") (pintype "bidirectional"))
      (node (ref "HALL-8-6") (pin "3") (pinfunction "GND_3") (pintype "bidirectional"))
      (node (ref "HALL-8-7") (pin "3") (pinfunction "GND_3") (pintype "bidirectional"))
      (node (ref "HALL-8-8") (pin "3") (pinfunction "GND_3") (pintype "bidirectional"))
      (node (ref "HALL1-3") (pin "3") (pinfunction "GND_3") (pintype "bidirectional"))
      (node (ref "HALL1-8") (pin "3") (pinfunction "GND_3") (pintype "bidirectional"))
      (node (ref "HALL2-5") (pin "3") (pinfunction "GND_3") (pintype "bidirectional"))
      (node (ref "HALL4-3") (pin "3") (pinfunction "GND_3") (pintype "bidirectional"))
      (node (ref "HALL4-4") (pin "3") (pinfunction "GND_3") (pintype "bidirectional"))
      (node (ref "HALL5-6") (pin "3") (pinfunction "GND_3") (pintype "bidirectional"))
      (node (ref "HALL6-6") (pin "3") (pinfunction "GND_3") (pintype "bidirectional"))
      (node (ref "HALL6-7") (pin "3") (pinfunction "GND_3") (pintype "bidirectional"))
      (node (ref "HALL7-1") (pin "3") (pinfunction "GND_3") (pintype "bidirectional"))
      (node (ref "HALL7-2") (pin "3") (pinfunction "GND_3") (pintype "bidirectional"))
      (node (ref "HALL7-7") (pin "3") (pinfunction "GND_3") (pintype "bidirectional"))
      (node (ref "IC1") (pin "11") (pinfunction "GND_11") (pintype "power_in"))
      (node (ref "IC1") (pin "32") (pinfunction "GND1_32") (pintype "power_in"))
      (node (ref "IC1") (pin "62") (pinfunction "GND2_62") (pintype "power_in"))
      (node (ref "IC1") (pin "81") (pinfunction "GND3_81") (pintype "power_in"))
      (node (ref "IC1") (pin "99") (pinfunction "AGND_99") (pintype "power_in"))
      (node (ref "IC2") (pin "3") (pinfunction "GND_3") (pintype "power_in"))
      (node (ref "IC2") (pin "5") (pinfunction "~{ON}/OFF_5") (pintype "input"))
      (node (ref "IC3") (pin "3") (pinfunction "GND_3") (pintype "passive"))
      (node (ref "IC4") (pin "3") (pinfunction "GND_3") (pintype "power_in"))
      (node (ref "IC4") (pin "5") (pinfunction "~{ON}/OFF_5") (pintype "input"))
      (node (ref "IC5") (pin "3") (pinfunction "GND_3") (pintype "power_in"))
      (node (ref "IC5") (pin "5") (pinfunction "~{ON}/OFF_5") (pintype "input"))
      (node (ref "IC6") (pin "11") (pinfunction "A0_11") (pintype "input"))
      (node (ref "IC6") (pin "12") (pinfunction "A1_12") (pintype "input"))
      (node (ref "IC6") (pin "13") (pinfunction "A2_13") (pintype "input"))
      (node (ref "IC6") (pin "6") (pinfunction "VSS_6") (pintype "power_in"))
      (node (ref "IC7") (pin "12") (pinfunction "A1_12") (pintype "input"))
      (node (ref "IC7") (pin "13") (pinfunction "A2_13") (pintype "input"))
      (node (ref "IC7") (pin "6") (pinfunction "VSS_6") (pintype "power_in"))
      (node (ref "IC8") (pin "11") (pinfunction "A0_11") (pintype "input"))
      (node (ref "IC8") (pin "13") (pinfunction "A2_13") (pintype "input"))
      (node (ref "IC8") (pin "6") (pinfunction "VSS_6") (pintype "power_in"))
      (node (ref "IC9") (pin "13") (pinfunction "A2_13") (pintype "input"))
      (node (ref "IC9") (pin "6") (pinfunction "VSS_6") (pintype "power_in"))
      (node (ref "ICSP") (pin "6") (pinfunction "6_6") (pintype "bidirectional"))
      (node (ref "J3") (pin "GND") (pinfunction "GND_GND") (pintype "power_in"))
      (node (ref "J3") (pin "SHLD1") (pinfunction "SHIELD_SHLD1") (pintype "bidirectional"))
      (node (ref "J3") (pin "SHLD2") (pinfunction "SHIELD_SHLD2") (pintype "bidirectional"))
      (node (ref "LED1") (pin "C") (pinfunction "C_C") (pintype "passive"))
      (node (ref "LED1-1") (pin "3-GND") (pinfunction "GND_3-GND") (pintype "power_in"))
      (node (ref "LED1-2") (pin "3-GND") (pinfunction "GND_3-GND") (pintype "power_in"))
      (node (ref "LED1-3") (pin "3-GND") (pinfunction "GND_3-GND") (pintype "power_in"))
      (node (ref "LED1-4") (pin "3-GND") (pinfunction "GND_3-GND") (pintype "power_in"))
      (node (ref "LED1-5") (pin "3-GND") (pinfunction "GND_3-GND") (pintype "power_in"))
      (node (ref "LED1-6") (pin "3-GND") (pinfunction "GND_3-GND") (pintype "power_in"))
      (node (ref "LED1-7") (pin "3-GND") (pinfunction "GND_3-GND") (pintype "power_in"))
      (node (ref "LED1-8") (pin "3-GND") (pinfunction "GND_3-GND") (pintype "power_in"))
      (node (ref "LED2") (pin "C") (pinfunction "C_C") (pintype "passive"))
      (node (ref "LED2-1") (pin "3-GND") (pinfunction "GND_3-GND") (pintype "power_in"))
      (node (ref "LED2-2") (pin "3-GND") (pinfunction "GND_3-GND") (pintype "power_in"))
      (node (ref "LED2-3") (pin "3-GND") (pinfunction "GND_3-GND") (pintype "power_in"))
      (node (ref "LED2-4") (pin "3-GND") (pinfunction "GND_3-GND") (pintype "power_in"))
      (node (ref "LED2-5") (pin "3-GND") (pinfunction "GND_3-GND") (pintype "power_in"))
      (node (ref "LED2-6") (pin "3-GND") (pinfunction "GND_3-GND") (pintype "power_in"))
      (node (ref "LED2-7") (pin "3-GND") (pinfunction "GND_3-GND") (pintype "power_in"))
      (node (ref "LED2-8") (pin "3-GND") (pinfunction "GND_3-GND") (pintype "power_in"))
      (node (ref "LED3-1") (pin "3-GND") (pinfunction "GND_3-GND") (pintype "power_in"))
      (node (ref "LED3-2") (pin "3-GND") (pinfunction "GND_3-GND") (pintype "power_in"))
      (node (ref "LED3-3") (pin "3-GND") (pinfunction "GND_3-GND") (pintype "power_in"))
      (node (ref "LED3-4") (pin "3-GND") (pinfunction "GND_3-GND") (pintype "power_in"))
      (node (ref "LED3-5") (pin "3-GND") (pinfunction "GND_3-GND") (pintype "power_in"))
      (node (ref "LED3-6") (pin "3-GND") (pinfunction "GND_3-GND") (pintype "power_in"))
      (node (ref "LED3-7") (pin "3-GND") (pinfunction "GND_3-GND") (pintype "power_in"))
      (node (ref "LED3-8") (pin "3-GND") (pinfunction "GND_3-GND") (pintype "power_in"))
      (node (ref "LED4-1") (pin "3-GND") (pinfunction "GND_3-GND") (pintype "power_in"))
      (node (ref "LED4-2") (pin "3-GND") (pinfunction "GND_3-GND") (pintype "power_in"))
      (node (ref "LED4-3") (pin "3-GND") (pinfunction "GND_3-GND") (pintype "power_in"))
      (node (ref "LED4-4") (pin "3-GND") (pinfunction "GND_3-GND") (pintype "power_in"))
      (node (ref "LED4-5") (pin "3-GND") (pinfunction "GND_3-GND") (pintype "power_in"))
      (node (ref "LED4-6") (pin "3-GND") (pinfunction "GND_3-GND") (pintype "power_in"))
      (node (ref "LED4-7") (pin "3-GND") (pinfunction "GND_3-GND") (pintype "power_in"))
      (node (ref "LED4-8") (pin "3-GND") (pinfunction "GND_3-GND") (pintype "power_in"))
      (node (ref "LED5-1") (pin "3-GND") (pinfunction "GND_3-GND") (pintype "power_in"))
      (node (ref "LED5-2") (pin "3-GND") (pinfunction "GND_3-GND") (pintype "power_in"))
      (node (ref "LED5-3") (pin "3-GND") (pinfunction "GND_3-GND") (pintype "power_in"))
      (node (ref "LED5-4") (pin "3-GND") (pinfunction "GND_3-GND") (pintype "power_in"))
      (node (ref "LED5-5") (pin "3-GND") (pinfunction "GND_3-GND") (pintype "power_in"))
      (node (ref "LED5-6") (pin "3-GND") (pinfunction "GND_3-GND") (pintype "power_in"))
      (node (ref "LED5-7") (pin "3-GND") (pinfunction "GND_3-GND") (pintype "power_in"))
      (node (ref "LED5-8") (pin "3-GND") (pinfunction "GND_3-GND") (pintype "power_in"))
      (node (ref "LED6-1") (pin "3-GND") (pinfunction "GND_3-GND") (pintype "power_in"))
      (node (ref "LED6-2") (pin "3-GND") (pinfunction "GND_3-GND") (pintype "power_in"))
      (node (ref "LED6-3") (pin "3-GND") (pinfunction "GND_3-GND") (pintype "power_in"))
      (node (ref "LED6-4") (pin "3-GND") (pinfunction "GND_3-GND") (pintype "power_in"))
      (node (ref "LED6-5") (pin "3-GND") (pinfunction "GND_3-GND") (pintype "power_in"))
      (node (ref "LED6-6") (pin "3-GND") (pinfunction "GND_3-GND") (pintype "power_in"))
      (node (ref "LED6-7") (pin "3-GND") (pinfunction "GND_3-GND") (pintype "power_in"))
      (node (ref "LED6-8") (pin "3-GND") (pinfunction "GND_3-GND") (pintype "power_in"))
      (node (ref "LED7-1") (pin "3-GND") (pinfunction "GND_3-GND") (pintype "power_in"))
      (node (ref "LED7-2") (pin "3-GND") (pinfunction "GND_3-GND") (pintype "power_in"))
      (node (ref "LED7-3") (pin "3-GND") (pinfunction "GND_3-GND") (pintype "power_in"))
      (node (ref "LED7-4") (pin "3-GND") (pinfunction "GND_3-GND") (pintype "power_in"))
      (node (ref "LED7-5") (pin "3-GND") (pinfunction "GND_3-GND") (pintype "power_in"))
      (node (ref "LED7-6") (pin "3-GND") (pinfunction "GND_3-GND") (pintype "power_in"))
      (node (ref "LED7-7") (pin "3-GND") (pinfunction "GND_3-GND") (pintype "power_in"))
      (node (ref "LED7-8") (pin "3-GND") (pinfunction "GND_3-GND") (pintype "power_in"))
      (node (ref "LED8-1") (pin "3-GND") (pinfunction "GND_3-GND") (pintype "power_in"))
      (node (ref "LED8-2") (pin "3-GND") (pinfunction "GND_3-GND") (pintype "power_in"))
      (node (ref "LED8-3") (pin "3-GND") (pinfunction "GND_3-GND") (pintype "power_in"))
      (node (ref "LED8-4") (pin "3-GND") (pinfunction "GND_3-GND") (pintype "power_in"))
      (node (ref "LED8-5") (pin "3-GND") (pinfunction "GND_3-GND") (pintype "power_in"))
      (node (ref "LED8-6") (pin "3-GND") (pinfunction "GND_3-GND") (pintype "power_in"))
      (node (ref "LED8-7") (pin "3-GND") (pinfunction "GND_3-GND") (pintype "power_in"))
      (node (ref "LED8-8") (pin "3-GND") (pinfunction "GND_3-GND") (pintype "power_in"))
      (node (ref "R11") (pin "1") (pinfunction "1_1") (pintype "passive"))
      (node (ref "R14") (pin "1") (pinfunction "1_1") (pintype "passive"))
      (node (ref "R2") (pin "1") (pinfunction "1_1") (pintype "passive"))
      (node (ref "S1") (pin "1") (pinfunction "1_1") (pintype "passive"))
      (node (ref "S1") (pin "2") (pinfunction "2_2") (pintype "passive"))
      (node (ref "STEPDRV1") (pin "15") (pinfunction "GND_15") (pintype "power_in"))
      (node (ref "STEPDRV1") (pin "9") (pinfunction "GND_9") (pintype "power_in"))
      (node (ref "STEPDRV2") (pin "15") (pinfunction "GND_15") (pintype "power_in"))
      (node (ref "STEPDRV2") (pin "9") (pinfunction "GND_9") (pintype "power_in"))
      (node (ref "U$50") (pin "2") (pinfunction "2_2") (pintype "passive"))
      (node (ref "U1") (pin "18") (pinfunction "GND2_18") (pintype "power_in"))
      (node (ref "U1") (pin "21") (pinfunction "GND3_21") (pintype "power_in"))
      (node (ref "U1") (pin "25") (pinfunction "AGND_25") (pintype "power_in"))
      (node (ref "U1") (pin "7") (pinfunction "GND1_7") (pintype "power_in"))
    )
    (net (code "70") (name "HALL-1-1") (class "Default")
      (node (ref "HALL-1-1") (pin "2") (pinfunction "OUT_2") (pintype "bidirectional"))
      (node (ref "IC6") (pin "17") (pinfunction "GPA0_17") (pintype "bidirectional"))
    )
    (net (code "71") (name "HALL-1-2") (class "Default")
      (node (ref "HALL-1-2") (pin "2") (pinfunction "OUT_2") (pintype "bidirectional"))
      (node (ref "IC6") (pin "18") (pinfunction "GPA1_18") (pintype "bidirectional"))
    )
    (net (code "72") (name "HALL-1-3") (class "Default")
      (node (ref "HALL1-3") (pin "2") (pinfunction "OUT_2") (pintype "bidirectional"))
      (node (ref "IC6") (pin "19") (pinfunction "GPA2_19") (pintype "bidirectional"))
    )
    (net (code "73") (name "HALL-1-4") (class "Default")
      (node (ref "HALL-1-4") (pin "2") (pinfunction "OUT_2") (pintype "bidirectional"))
      (node (ref "IC6") (pin "20") (pinfunction "GPA3_20") (pintype "bidirectional"))
    )
    (net (code "74") (name "HALL-1-5") (class "Default")
      (node (ref "HALL-1-5") (pin "2") (pinfunction "OUT_2") (pintype "bidirectional"))
      (node (ref "IC6") (pin "21") (pinfunction "GPA4_21") (pintype "bidirectional"))
    )
    (net (code "75") (name "HALL-1-6") (class "Default")
      (node (ref "HALL-1-6") (pin "2") (pinfunction "OUT_2") (pintype "bidirectional"))
      (node (ref "IC6") (pin "22") (pinfunction "GPA5_22") (pintype "bidirectional"))
    )
    (net (code "76") (name "HALL-1-7") (class "Default")
      (node (ref "HALL-1-7") (pin "2") (pinfunction "OUT_2") (pintype "bidirectional"))
      (node (ref "IC6") (pin "23") (pinfunction "GPA6_23") (pintype "bidirectional"))
    )
    (net (code "77") (name "HALL-1-8") (class "Default")
      (node (ref "HALL1-8") (pin "2") (pinfunction "OUT_2") (pintype "bidirectional"))
      (node (ref "IC6") (pin "24") (pinfunction "GPA7_24") (pintype "bidirectional"))
    )
    (net (code "78") (name "HALL-2-1") (class "Default")
      (node (ref "HALL-2-1") (pin "2") (pinfunction "OUT_2") (pintype "bidirectional"))
      (node (ref "IC6") (pin "25") (pinfunction "GPB0_25") (pintype "bidirectional"))
    )
    (net (code "79") (name "HALL-2-2") (class "Default")
      (node (ref "HALL-2-2") (pin "2") (pinfunction "OUT_2") (pintype "bidirectional"))
      (node (ref "IC6") (pin "26") (pinfunction "GPB1_26") (pintype "bidirectional"))
    )
    (net (code "80") (name "HALL-2-3") (class "Default")
      (node (ref "HALL-2-3") (pin "2") (pinfunction "OUT_2") (pintype "bidirectional"))
      (node (ref "IC6") (pin "27") (pinfunction "GPB2_27") (pintype "bidirectional"))
    )
    (net (code "81") (name "HALL-2-4") (class "Default")
      (node (ref "HALL-2-4") (pin "2") (pinfunction "OUT_2") (pintype "bidirectional"))
      (node (ref "IC6") (pin "28") (pinfunction "GPB3_28") (pintype "bidirectional"))
    )
    (net (code "82") (name "HALL-2-5") (class "Default")
      (node (ref "HALL2-5") (pin "2") (pinfunction "OUT_2") (pintype "bidirectional"))
      (node (ref "IC6") (pin "1") (pinfunction "GPB4_1") (pintype "bidirectional"))
    )
    (net (code "83") (name "HALL-2-6") (class "Default")
      (node (ref "HALL-2-6") (pin "2") (pinfunction "OUT_2") (pintype "bidirectional"))
      (node (ref "IC6") (pin "2") (pinfunction "GPB5_2") (pintype "bidirectional"))
    )
    (net (code "84") (name "HALL-2-7") (class "Default")
      (node (ref "HALL-2-7") (pin "2") (pinfunction "OUT_2") (pintype "bidirectional"))
      (node (ref "IC6") (pin "3") (pinfunction "GPB6_3") (pintype "bidirectional"))
    )
    (net (code "85") (name "HALL-2-8") (class "Default")
      (node (ref "HALL-2-8") (pin "2") (pinfunction "OUT_2") (pintype "bidirectional"))
      (node (ref "IC6") (pin "4") (pinfunction "GPB7_4") (pintype "bidirectional"))
    )
    (net (code "86") (name "HALL-3-1") (class "Default")
      (node (ref "HALL-3-1") (pin "2") (pinfunction "OUT_2") (pintype "bidirectional"))
      (node (ref "IC7") (pin "17") (pinfunction "GPA0_17") (pintype "bidirectional"))
    )
    (net (code "87") (name "HALL-3-2") (class "Default")
      (node (ref "HALL-3-2") (pin "2") (pinfunction "OUT_2") (pintype "bidirectional"))
      (node (ref "IC7") (pin "18") (pinfunction "GPA1_18") (pintype "bidirectional"))
    )
    (net (code "88") (name "HALL-3-3") (class "Default")
      (node (ref "HALL-3-3") (pin "2") (pinfunction "OUT_2") (pintype "bidirectional"))
      (node (ref "IC7") (pin "19") (pinfunction "GPA2_19") (pintype "bidirectional"))
    )
    (net (code "89") (name "HALL-3-4") (class "Default")
      (node (ref "HALL-3-4") (pin "2") (pinfunction "OUT_2") (pintype "bidirectional"))
      (node (ref "IC7") (pin "20") (pinfunction "GPA3_20") (pintype "bidirectional"))
    )
    (net (code "90") (name "HALL-3-5") (class "Default")
      (node (ref "HALL-3-5") (pin "2") (pinfunction "OUT_2") (pintype "bidirectional"))
      (node (ref "IC7") (pin "21") (pinfunction "GPA4_21") (pintype "bidirectional"))
    )
    (net (code "91") (name "HALL-3-6") (class "Default")
      (node (ref "HALL-3-6") (pin "2") (pinfunction "OUT_2") (pintype "bidirectional"))
      (node (ref "IC7") (pin "22") (pinfunction "GPA5_22") (pintype "bidirectional"))
    )
    (net (code "92") (name "HALL-3-7") (class "Default")
      (node (ref "HALL-3-7") (pin "2") (pinfunction "OUT_2") (pintype "bidirectional"))
      (node (ref "IC7") (pin "23") (pinfunction "GPA6_23") (pintype "bidirectional"))
    )
    (net (code "93") (name "HALL-3-8") (class "Default")
      (node (ref "HALL-3-8") (pin "2") (pinfunction "OUT_2") (pintype "bidirectional"))
      (node (ref "IC7") (pin "24") (pinfunction "GPA7_24") (pintype "bidirectional"))
    )
    (net (code "94") (name "HALL-4-1") (class "Default")
      (node (ref "HALL-4-1") (pin "2") (pinfunction "OUT_2") (pintype "bidirectional"))
      (node (ref "IC7") (pin "25") (pinfunction "GPB0_25") (pintype "bidirectional"))
    )
    (net (code "95") (name "HALL-4-2") (class "Default")
      (node (ref "HALL-4-2") (pin "2") (pinfunction "OUT_2") (pintype "bidirectional"))
      (node (ref "IC7") (pin "26") (pinfunction "GPB1_26") (pintype "bidirectional"))
    )
    (net (code "96") (name "HALL-4-3") (class "Default")
      (node (ref "HALL4-3") (pin "2") (pinfunction "OUT_2") (pintype "bidirectional"))
      (node (ref "IC7") (pin "27") (pinfunction "GPB2_27") (pintype "bidirectional"))
    )
    (net (code "97") (name "HALL-4-4") (class "Default")
      (node (ref "HALL4-4") (pin "2") (pinfunction "OUT_2") (pintype "bidirectional"))
      (node (ref "IC7") (pin "28") (pinfunction "GPB3_28") (pintype "bidirectional"))
    )
    (net (code "98") (name "HALL-4-5") (class "Default")
      (node (ref "HALL-4-5") (pin "2") (pinfunction "OUT_2") (pintype "bidirectional"))
      (node (ref "IC7") (pin "1") (pinfunction "GPB4_1") (pintype "bidirectional"))
    )
    (net (code "99") (name "HALL-4-6") (class "Default")
      (node (ref "HALL-4-6") (pin "2") (pinfunction "OUT_2") (pintype "bidirectional"))
      (node (ref "IC7") (pin "2") (pinfunction "GPB5_2") (pintype "bidirectional"))
    )
    (net (code "100") (name "HALL-4-7") (class "Default")
      (node (ref "HALL-4-7") (pin "2") (pinfunction "OUT_2") (pintype "bidirectional"))
      (node (ref "IC7") (pin "3") (pinfunction "GPB6_3") (pintype "bidirectional"))
    )
    (net (code "101") (name "HALL-4-8") (class "Default")
      (node (ref "HALL-4-8") (pin "2") (pinfunction "OUT_2") (pintype "bidirectional"))
      (node (ref "IC7") (pin "4") (pinfunction "GPB7_4") (pintype "bidirectional"))
    )
    (net (code "102") (name "HALL-5-1") (class "Default")
      (node (ref "HALL-5-1") (pin "2") (pinfunction "OUT_2") (pintype "bidirectional"))
      (node (ref "IC8") (pin "17") (pinfunction "GPA0_17") (pintype "bidirectional"))
    )
    (net (code "103") (name "HALL-5-2") (class "Default")
      (node (ref "HALL-5-2") (pin "2") (pinfunction "OUT_2") (pintype "bidirectional"))
      (node (ref "IC8") (pin "18") (pinfunction "GPA1_18") (pintype "bidirectional"))
    )
    (net (code "104") (name "HALL-5-3") (class "Default")
      (node (ref "HALL-5-3") (pin "2") (pinfunction "OUT_2") (pintype "bidirectional"))
      (node (ref "IC8") (pin "19") (pinfunction "GPA2_19") (pintype "bidirectional"))
    )
    (net (code "105") (name "HALL-5-4") (class "Default")
      (node (ref "HALL-5-4") (pin "2") (pinfunction "OUT_2") (pintype "bidirectional"))
      (node (ref "IC8") (pin "20") (pinfunction "GPA3_20") (pintype "bidirectional"))
    )
    (net (code "106") (name "HALL-5-5") (class "Default")
      (node (ref "HALL-5-5") (pin "2") (pinfunction "OUT_2") (pintype "bidirectional"))
      (node (ref "IC8") (pin "21") (pinfunction "GPA4_21") (pintype "bidirectional"))
    )
    (net (code "107") (name "HALL-5-6") (class "Default")
      (node (ref "HALL5-6") (pin "2") (pinfunction "OUT_2") (pintype "bidirectional"))
      (node (ref "IC8") (pin "22") (pinfunction "GPA5_22") (pintype "bidirectional"))
    )
    (net (code "108") (name "HALL-5-7") (class "Default")
      (node (ref "HALL-5-7") (pin "2") (pinfunction "OUT_2") (pintype "bidirectional"))
      (node (ref "IC8") (pin "23") (pinfunction "GPA6_23") (pintype "bidirectional"))
    )
    (net (code "109") (name "HALL-5-8") (class "Default")
      (node (ref "HALL-5-8") (pin "2") (pinfunction "OUT_2") (pintype "bidirectional"))
      (node (ref "IC8") (pin "24") (pinfunction "GPA7_24") (pintype "bidirectional"))
    )
    (net (code "110") (name "HALL-6-1") (class "Default")
      (node (ref "HALL-6-1") (pin "2") (pinfunction "OUT_2") (pintype "bidirectional"))
      (node (ref "IC8") (pin "25") (pinfunction "GPB0_25") (pintype "bidirectional"))
    )
    (net (code "111") (name "HALL-6-2") (class "Default")
      (node (ref "HALL-6-2") (pin "2") (pinfunction "OUT_2") (pintype "bidirectional"))
      (node (ref "IC8") (pin "26") (pinfunction "GPB1_26") (pintype "bidirectional"))
    )
    (net (code "112") (name "HALL-6-3") (class "Default")
      (node (ref "HALL-6-3") (pin "2") (pinfunction "OUT_2") (pintype "bidirectional"))
      (node (ref "IC8") (pin "27") (pinfunction "GPB2_27") (pintype "bidirectional"))
    )
    (net (code "113") (name "HALL-6-4") (class "Default")
      (node (ref "HALL-6-4") (pin "2") (pinfunction "OUT_2") (pintype "bidirectional"))
      (node (ref "IC8") (pin "28") (pinfunction "GPB3_28") (pintype "bidirectional"))
    )
    (net (code "114") (name "HALL-6-5") (class "Default")
      (node (ref "HALL-6-5") (pin "2") (pinfunction "OUT_2") (pintype "bidirectional"))
      (node (ref "IC8") (pin "1") (pinfunction "GPB4_1") (pintype "bidirectional"))
    )
    (net (code "115") (name "HALL-6-6") (class "Default")
      (node (ref "HALL6-6") (pin "2") (pinfunction "OUT_2") (pintype "bidirectional"))
      (node (ref "IC8") (pin "2") (pinfunction "GPB5_2") (pintype "bidirectional"))
    )
    (net (code "116") (name "HALL-6-7") (class "Default")
      (node (ref "HALL6-7") (pin "2") (pinfunction "OUT_2") (pintype "bidirectional"))
      (node (ref "IC8") (pin "3") (pinfunction "GPB6_3") (pintype "bidirectional"))
    )
    (net (code "117") (name "HALL-6-8") (class "Default")
      (node (ref "HALL-6-8") (pin "2") (pinfunction "OUT_2") (pintype "bidirectional"))
      (node (ref "IC8") (pin "4") (pinfunction "GPB7_4") (pintype "bidirectional"))
    )
    (net (code "118") (name "HALL-7-1") (class "Default")
      (node (ref "HALL7-1") (pin "2") (pinfunction "OUT_2") (pintype "bidirectional"))
      (node (ref "IC9") (pin "17") (pinfunction "GPA0_17") (pintype "bidirectional"))
    )
    (net (code "119") (name "HALL-7-2") (class "Default")
      (node (ref "HALL7-2") (pin "2") (pinfunction "OUT_2") (pintype "bidirectional"))
      (node (ref "IC9") (pin "18") (pinfunction "GPA1_18") (pintype "bidirectional"))
    )
    (net (code "120") (name "HALL-7-3") (class "Default")
      (node (ref "HALL-7-3") (pin "2") (pinfunction "OUT_2") (pintype "bidirectional"))
      (node (ref "IC9") (pin "19") (pinfunction "GPA2_19") (pintype "bidirectional"))
    )
    (net (code "121") (name "HALL-7-4") (class "Default")
      (node (ref "HALL-7-4") (pin "2") (pinfunction "OUT_2") (pintype "bidirectional"))
      (node (ref "IC9") (pin "20") (pinfunction "GPA3_20") (pintype "bidirectional"))
    )
    (net (code "122") (name "HALL-7-5") (class "Default")
      (node (ref "HALL-7-5") (pin "2") (pinfunction "OUT_2") (pintype "bidirectional"))
      (node (ref "IC9") (pin "21") (pinfunction "GPA4_21") (pintype "bidirectional"))
    )
    (net (code "123") (name "HALL-7-6") (class "Default")
      (node (ref "HALL-7-6") (pin "2") (pinfunction "OUT_2") (pintype "bidirectional"))
      (node (ref "IC9") (pin "22") (pinfunction "GPA5_22") (pintype "bidirectional"))
    )
    (net (code "124") (name "HALL-7-7") (class "Default")
      (node (ref "HALL7-7") (pin "2") (pinfunction "OUT_2") (pintype "bidirectional"))
      (node (ref "IC9") (pin "23") (pinfunction "GPA6_23") (pintype "bidirectional"))
    )
    (net (code "125") (name "HALL-7-8") (class "Default")
      (node (ref "HALL-7-8") (pin "2") (pinfunction "OUT_2") (pintype "bidirectional"))
      (node (ref "IC9") (pin "24") (pinfunction "GPA7_24") (pintype "bidirectional"))
    )
    (net (code "126") (name "HALL-8-1") (class "Default")
      (node (ref "HALL-8-1") (pin "2") (pinfunction "OUT_2") (pintype "bidirectional"))
      (node (ref "IC9") (pin "25") (pinfunction "GPB0_25") (pintype "bidirectional"))
    )
    (net (code "127") (name "HALL-8-2") (class "Default")
      (node (ref "HALL-8-2") (pin "2") (pinfunction "OUT_2") (pintype "bidirectional"))
      (node (ref "IC9") (pin "26") (pinfunction "GPB1_26") (pintype "bidirectional"))
    )
    (net (code "128") (name "HALL-8-3") (class "Default")
      (node (ref "HALL-8-3") (pin "2") (pinfunction "OUT_2") (pintype "bidirectional"))
      (node (ref "IC9") (pin "27") (pinfunction "GPB2_27") (pintype "bidirectional"))
    )
    (net (code "129") (name "HALL-8-4") (class "Default")
      (node (ref "HALL-8-4") (pin "2") (pinfunction "OUT_2") (pintype "bidirectional"))
      (node (ref "IC9") (pin "28") (pinfunction "GPB3_28") (pintype "bidirectional"))
    )
    (net (code "130") (name "HALL-8-5") (class "Default")
      (node (ref "HALL-8-5") (pin "2") (pinfunction "OUT_2") (pintype "bidirectional"))
      (node (ref "IC9") (pin "1") (pinfunction "GPB4_1") (pintype "bidirectional"))
    )
    (net (code "131") (name "HALL-8-6") (class "Default")
      (node (ref "HALL-8-6") (pin "2") (pinfunction "OUT_2") (pintype "bidirectional"))
      (node (ref "IC9") (pin "2") (pinfunction "GPB5_2") (pintype "bidirectional"))
    )
    (net (code "132") (name "HALL-8-7") (class "Default")
      (node (ref "HALL-8-7") (pin "2") (pinfunction "OUT_2") (pintype "bidirectional"))
      (node (ref "IC9") (pin "3") (pinfunction "GPB6_3") (pintype "bidirectional"))
    )
    (net (code "133") (name "HALL-8-8") (class "Default")
      (node (ref "HALL-8-8") (pin "2") (pinfunction "OUT_2") (pintype "bidirectional"))
      (node (ref "IC9") (pin "4") (pinfunction "GPB7_4") (pintype "bidirectional"))
    )
    (net (code "134") (name "LED_MATRIX_DIN") (class "Default")
      (node (ref "IC1") (pin "25") (pinfunction "(OC1B/PCINT6)PB6_25") (pintype "bidirectional"))
      (node (ref "R12") (pin "2") (pinfunction "2_2") (pintype "passive"))
    )
    (net (code "135") (name "LED_SUPPLY") (class "Default")
      (node (ref "C1-1") (pin "2") (pinfunction "2_2") (pintype "passive"))
      (node (ref "C1-2") (pin "2") (pinfunction "2_2") (pintype "passive"))
      (node (ref "C1-3") (pin "2") (pinfunction "2_2") (pintype "passive"))
      (node (ref "C1-4") (pin "2") (pinfunction "2_2") (pintype "passive"))
      (node (ref "C1-5") (pin "2") (pinfunction "2_2") (pintype "passive"))
      (node (ref "C1-6") (pin "2") (pinfunction "2_2") (pintype "passive"))
      (node (ref "C1-7") (pin "2") (pinfunction "2_2") (pintype "passive"))
      (node (ref "C1-8") (pin "2") (pinfunction "2_2") (pintype "passive"))
      (node (ref "C2-1") (pin "2") (pinfunction "2_2") (pintype "passive"))
      (node (ref "C2-2") (pin "2") (pinfunction "2_2") (pintype "passive"))
      (node (ref "C2-3") (pin "2") (pinfunction "2_2") (pintype "passive"))
      (node (ref "C2-4") (pin "2") (pinfunction "2_2") (pintype "passive"))
      (node (ref "C2-5") (pin "2") (pinfunction "2_2") (pintype "passive"))
      (node (ref "C2-6") (pin "2") (pinfunction "2_2") (pintype "passive"))
      (node (ref "C2-7") (pin "2") (pinfunction "2_2") (pintype "passive"))
      (node (ref "C2-8") (pin "2") (pinfunction "2_2") (pintype "passive"))
      (node (ref "C22") (pin "+") (pinfunction "+_+") (pintype "passive"))
      (node (ref "C24") (pin "1") (pinfunction "1_1") (pintype "passive"))
      (node (ref "C3-1") (pin "2") (pinfunction "2_2") (pintype "passive"))
      (node (ref "C3-2") (pin "2") (pinfunction "2_2") (pintype "passive"))
      (node (ref "C3-3") (pin "2") (pinfunction "2_2") (pintype "passive"))
      (node (ref "C3-4") (pin "2") (pinfunction "2_2") (pintype "passive"))
      (node (ref "C3-5") (pin "2") (pinfunction "2_2") (pintype "passive"))
      (node (ref "C3-6") (pin "2") (pinfunction "2_2") (pintype "passive"))
      (node (ref "C3-7") (pin "2") (pinfunction "2_2") (pintype "passive"))
      (node (ref "C3-8") (pin "2") (pinfunction "2_2") (pintype "passive"))
      (node (ref "C4-1") (pin "2") (pinfunction "2_2") (pintype "passive"))
      (node (ref "C4-2") (pin "2") (pinfunction "2_2") (pintype "passive"))
      (node (ref "C4-3") (pin "2") (pinfunction "2_2") (pintype "passive"))
      (node (ref "C4-4") (pin "2") (pinfunction "2_2") (pintype "passive"))
      (node (ref "C4-5") (pin "2") (pinfunction "2_2") (pintype "passive"))
      (node (ref "C4-6") (pin "2") (pinfunction "2_2") (pintype "passive"))
      (node (ref "C4-7") (pin "2") (pinfunction "2_2") (pintype "passive"))
      (node (ref "C4-8") (pin "2") (pinfunction "2_2") (pintype "passive"))
      (node (ref "C5-1") (pin "2") (pinfunction "2_2") (pintype "passive"))
      (node (ref "C5-2") (pin "2") (pinfunction "2_2") (pintype "passive"))
      (node (ref "C5-3") (pin "2") (pinfunction "2_2") (pintype "passive"))
      (node (ref "C5-4") (pin "2") (pinfunction "2_2") (pintype "passive"))
      (node (ref "C5-5") (pin "2") (pinfunction "2_2") (pintype "passive"))
      (node (ref "C5-6") (pin "2") (pinfunction "2_2") (pintype "passive"))
      (node (ref "C5-7") (pin "2") (pinfunction "2_2") (pintype "passive"))
      (node (ref "C5-8") (pin "2") (pinfunction "2_2") (pintype "passive"))
      (node (ref "C6-1") (pin "2") (pinfunction "2_2") (pintype "passive"))
      (node (ref "C6-2") (pin "2") (pinfunction "2_2") (pintype "passive"))
      (node (ref "C6-3") (pin "2") (pinfunction "2_2") (pintype "passive"))
      (node (ref "C6-4") (pin "2") (pinfunction "2_2") (pintype "passive"))
      (node (ref "C6-5") (pin "2") (pinfunction "2_2") (pintype "passive"))
      (node (ref "C6-6") (pin "2") (pinfunction "2_2") (pintype "passive"))
      (node (ref "C6-7") (pin "2") (pinfunction "2_2") (pintype "passive"))
      (node (ref "C6-8") (pin "2") (pinfunction "2_2") (pintype "passive"))
      (node (ref "C7-1") (pin "2") (pinfunction "2_2") (pintype "passive"))
      (node (ref "C7-2") (pin "2") (pinfunction "2_2") (pintype "passive"))
      (node (ref "C7-3") (pin "2") (pinfunction "2_2") (pintype "passive"))
      (node (ref "C7-4") (pin "2") (pinfunction "2_2") (pintype "passive"))
      (node (ref "C7-5") (pin "2") (pinfunction "2_2") (pintype "passive"))
      (node (ref "C7-6") (pin "2") (pinfunction "2_2") (pintype "passive"))
      (node (ref "C7-7") (pin "2") (pinfunction "2_2") (pintype "passive"))
      (node (ref "C7-8") (pin "2") (pinfunction "2_2") (pintype "passive"))
      (node (ref "C8-1") (pin "2") (pinfunction "2_2") (pintype "passive"))
      (node (ref "C8-2") (pin "2") (pinfunction "2_2") (pintype "passive"))
      (node (ref "C8-3") (pin "2") (pinfunction "2_2") (pintype "passive"))
      (node (ref "C8-4\\") (pin "2") (pinfunction "2_2") (pintype "passive"))
      (node (ref "C8-5") (pin "2") (pinfunction "2_2") (pintype "passive"))
      (node (ref "C8-6") (pin "2") (pinfunction "2_2") (pintype "passive"))
      (node (ref "C8-7") (pin "2") (pinfunction "2_2") (pintype "passive"))
      (node (ref "C8-8") (pin "2") (pinfunction "2_2") (pintype "passive"))
      (node (ref "L3") (pin "2") (pinfunction "2_2") (pintype "passive"))
      (node (ref "LED1-1") (pin "1-VDD") (pinfunction "VDD_1-VDD") (pintype "power_in"))
      (node (ref "LED1-2") (pin "1-VDD") (pinfunction "VDD_1-VDD") (pintype "power_in"))
      (node (ref "LED1-3") (pin "1-VDD") (pinfunction "VDD_1-VDD") (pintype "power_in"))
      (node (ref "LED1-4") (pin "1-VDD") (pinfunction "VDD_1-VDD") (pintype "power_in"))
      (node (ref "LED1-5") (pin "1-VDD") (pinfunction "VDD_1-VDD") (pintype "power_in"))
      (node (ref "LED1-6") (pin "1-VDD") (pinfunction "VDD_1-VDD") (pintype "power_in"))
      (node (ref "LED1-7") (pin "1-VDD") (pinfunction "VDD_1-VDD") (pintype "power_in"))
      (node (ref "LED1-8") (pin "1-VDD") (pinfunction "VDD_1-VDD") (pintype "power_in"))
      (node (ref "LED2-1") (pin "1-VDD") (pinfunction "VDD_1-VDD") (pintype "power_in"))
      (node (ref "LED2-2") (pin "1-VDD") (pinfunction "VDD_1-VDD") (pintype "power_in"))
      (node (ref "LED2-3") (pin "1-VDD") (pinfunction "VDD_1-VDD") (pintype "power_in"))
      (node (ref "LED2-4") (pin "1-VDD") (pinfunction "VDD_1-VDD") (pintype "power_in"))
      (node (ref "LED2-5") (pin "1-VDD") (pinfunction "VDD_1-VDD") (pintype "power_in"))
      (node (ref "LED2-6") (pin "1-VDD") (pinfunction "VDD_1-VDD") (pintype "power_in"))
      (node (ref "LED2-7") (pin "1-VDD") (pinfunction "VDD_1-VDD") (pintype "power_in"))
      (node (ref "LED2-8") (pin "1-VDD") (pinfunction "VDD_1-VDD") (pintype "power_in"))
      (node (ref "LED3-1") (pin "1-VDD") (pinfunction "VDD_1-VDD") (pintype "power_in"))
      (node (ref "LED3-2") (pin "1-VDD") (pinfunction "VDD_1-VDD") (pintype "power_in"))
      (node (ref "LED3-3") (pin "1-VDD") (pinfunction "VDD_1-VDD") (pintype "power_in"))
      (node (ref "LED3-4") (pin "1-VDD") (pinfunction "VDD_1-VDD") (pintype "power_in"))
      (node (ref "LED3-5") (pin "1-VDD") (pinfunction "VDD_1-VDD") (pintype "power_in"))
      (node (ref "LED3-6") (pin "1-VDD") (pinfunction "VDD_1-VDD") (pintype "power_in"))
      (node (ref "LED3-7") (pin "1-VDD") (pinfunction "VDD_1-VDD") (pintype "power_in"))
      (node (ref "LED3-8") (pin "1-VDD") (pinfunction "VDD_1-VDD") (pintype "power_in"))
      (node (ref "LED4-1") (pin "1-VDD") (pinfunction "VDD_1-VDD") (pintype "power_in"))
      (node (ref "LED4-2") (pin "1-VDD") (pinfunction "VDD_1-VDD") (pintype "power_in"))
      (node (ref "LED4-3") (pin "1-VDD") (pinfunction "VDD_1-VDD") (pintype "power_in"))
      (node (ref "LED4-4") (pin "1-VDD") (pinfunction "VDD_1-VDD") (pintype "power_in"))
      (node (ref "LED4-5") (pin "1-VDD") (pinfunction "VDD_1-VDD") (pintype "power_in"))
      (node (ref "LED4-6") (pin "1-VDD") (pinfunction "VDD_1-VDD") (pintype "power_in"))
      (node (ref "LED4-7") (pin "1-VDD") (pinfunction "VDD_1-VDD") (pintype "power_in"))
      (node (ref "LED4-8") (pin "1-VDD") (pinfunction "VDD_1-VDD") (pintype "power_in"))
      (node (ref "LED5-1") (pin "1-VDD") (pinfunction "VDD_1-VDD") (pintype "power_in"))
      (node (ref "LED5-2") (pin "1-VDD") (pinfunction "VDD_1-VDD") (pintype "power_in"))
      (node (ref "LED5-3") (pin "1-VDD") (pinfunction "VDD_1-VDD") (pintype "power_in"))
      (node (ref "LED5-4") (pin "1-VDD") (pinfunction "VDD_1-VDD") (pintype "power_in"))
      (node (ref "LED5-5") (pin "1-VDD") (pinfunction "VDD_1-VDD") (pintype "power_in"))
      (node (ref "LED5-6") (pin "1-VDD") (pinfunction "VDD_1-VDD") (pintype "power_in"))
      (node (ref "LED5-7") (pin "1-VDD") (pinfunction "VDD_1-VDD") (pintype "power_in"))
      (node (ref "LED5-8") (pin "1-VDD") (pinfunction "VDD_1-VDD") (pintype "power_in"))
      (node (ref "LED6-1") (pin "1-VDD") (pinfunction "VDD_1-VDD") (pintype "power_in"))
      (node (ref "LED6-2") (pin "1-VDD") (pinfunction "VDD_1-VDD") (pintype "power_in"))
      (node (ref "LED6-3") (pin "1-VDD") (pinfunction "VDD_1-VDD") (pintype "power_in"))
      (node (ref "LED6-4") (pin "1-VDD") (pinfunction "VDD_1-VDD") (pintype "power_in"))
      (node (ref "LED6-5") (pin "1-VDD") (pinfunction "VDD_1-VDD") (pintype "power_in"))
      (node (ref "LED6-6") (pin "1-VDD") (pinfunction "VDD_1-VDD") (pintype "power_in"))
      (node (ref "LED6-7") (pin "1-VDD") (pinfunction "VDD_1-VDD") (pintype "power_in"))
      (node (ref "LED6-8") (pin "1-VDD") (pinfunction "VDD_1-VDD") (pintype "power_in"))
      (node (ref "LED7-1") (pin "1-VDD") (pinfunction "VDD_1-VDD") (pintype "power_in"))
      (node (ref "LED7-2") (pin "1-VDD") (pinfunction "VDD_1-VDD") (pintype "power_in"))
      (node (ref "LED7-3") (pin "1-VDD") (pinfunction "VDD_1-VDD") (pintype "power_in"))
      (node (ref "LED7-4") (pin "1-VDD") (pinfunction "VDD_1-VDD") (pintype "power_in"))
      (node (ref "LED7-5") (pin "1-VDD") (pinfunction "VDD_1-VDD") (pintype "power_in"))
      (node (ref "LED7-6") (pin "1-VDD") (pinfunction "VDD_1-VDD") (pintype "power_in"))
      (node (ref "LED7-7") (pin "1-VDD") (pinfunction "VDD_1-VDD") (pintype "power_in"))
      (node (ref "LED7-8") (pin "1-VDD") (pinfunction "VDD_1-VDD") (pintype "power_in"))
      (node (ref "LED8-1") (pin "1-VDD") (pinfunction "VDD_1-VDD") (pintype "power_in"))
      (node (ref "LED8-2") (pin "1-VDD") (pinfunction "VDD_1-VDD") (pintype "power_in"))
      (node (ref "LED8-3") (pin "1-VDD") (pinfunction "VDD_1-VDD") (pintype "power_in"))
      (node (ref "LED8-4") (pin "1-VDD") (pinfunction "VDD_1-VDD") (pintype "power_in"))
      (node (ref "LED8-5") (pin "1-VDD") (pinfunction "VDD_1-VDD") (pintype "power_in"))
      (node (ref "LED8-6") (pin "1-VDD") (pinfunction "VDD_1-VDD") (pintype "power_in"))
      (node (ref "LED8-7") (pin "1-VDD") (pinfunction "VDD_1-VDD") (pintype "power_in"))
      (node (ref "LED8-8") (pin "1-VDD") (pinfunction "VDD_1-VDD") (pintype "power_in"))
      (node (ref "R13") (pin "E") (pinfunction "E_E") (pintype "passive"))
    )
    (net (code "136") (name "MOTORA_DIR") (class "Default")
      (node (ref "IC1") (pin "15") (pinfunction "PH3(OC4A)_15") (pintype "bidirectional"))
      (node (ref "STEPDRV1") (pin "8") (pinfunction "DIR_8") (pintype "input"))
    )
    (net (code "137") (name "MOTORA_EN") (class "Default")
      (node (ref "STEPDRV1") (pin "1") (pinfunction "~{ENABLE}_1") (pintype "input"))
    )
    (net (code "138") (name "MOTORA_STEP") (class "Default")
      (node (ref "IC1") (pin "7") (pinfunction "(OC3C/INT5)PE5_7") (pintype "bidirectional"))
      (node (ref "STEPDRV1") (pin "7") (pinfunction "STEP_7") (pintype "input"))
    )
    (net (code "139") (name "MOTORB_DIR") (class "Default")
      (node (ref "IC1") (pin "16") (pinfunction "PH4(OC4B)_16") (pintype "bidirectional"))
      (node (ref "STEPDRV2") (pin "8") (pinfunction "DIR_8") (pintype "input"))
    )
    (net (code "140") (name "MOTORB_EN") (class "Default")
      (node (ref "STEPDRV2") (pin "1") (pinfunction "~{ENABLE}_1") (pintype "input"))
    )
    (net (code "141") (name "MOTORB_STEP") (class "Default")
      (node (ref "IC1") (pin "5") (pinfunction "(OC3A/AIN1)PE3_5") (pintype "bidirectional"))
      (node (ref "STEPDRV2") (pin "7") (pinfunction "STEP_7") (pintype "input"))
    )
    (net (code "142") (name "MOTOR_A_SUPPLY") (class "Default")
      (node (ref "C14") (pin "+") (pinfunction "+_+") (pintype "passive"))
      (node (ref "C16") (pin "1") (pinfunction "1_1") (pintype "passive"))
      (node (ref "L1") (pin "2") (pinfunction "2_2") (pintype "passive"))
      (node (ref "R1") (pin "E") (pinfunction "E_E") (pintype "passive"))
      (node (ref "STEPDRV1") (pin "16") (pinfunction "VMOT_16") (pintype "power_in"))
    )
    (net (code "143") (name "MOTOR_B_SUPPLY") (class "Default")
      (node (ref "C18") (pin "+") (pinfunction "+_+") (pintype "passive"))
      (node (ref "C20") (pin "1") (pinfunction "1_1") (pintype "passive"))
      (node (ref "L2") (pin "2") (pinfunction "2_2") (pintype "passive"))
      (node (ref "R10") (pin "E") (pinfunction "E_E") (pintype "passive"))
      (node (ref "STEPDRV2") (pin "16") (pinfunction "VMOT_16") (pintype "power_in"))
    )
    (net (code "144") (name "Net-(C7-P$1)") (class "Default")
      (node (ref "C7") (pin "1") (pinfunction "P$1_1") (pintype "passive"))
      (node (ref "U1") (pin "2") (pinfunction "DTR_2") (pintype "bidirectional"))
    )
    (net (code "145") (name "Net-(CN1-PadPWR)") (class "Default")
      (node (ref "CN1") (pin "PWR") (pinfunction "PWR_PWR") (pintype "power_in"))
      (node (ref "F1") (pin "1A") (pinfunction "1A_1A") (pintype "passive"))
    )
    (net (code "146") (name "Net-(IC1-XTAL1)") (class "Default")
      (node (ref "IC1") (pin "34") (pinfunction "XTAL1_34") (pintype "input"))
      (node (ref "R16") (pin "2") (pinfunction "2_2") (pintype "passive"))
    )
    (net (code "147") (name "Net-(IC1-XTAL2)") (class "Default")
      (node (ref "IC1") (pin "33") (pinfunction "XTAL2_33") (pintype "output"))
      (node (ref "R15") (pin "2") (pinfunction "2_2") (pintype "passive"))
      (node (ref "U$50") (pin "1") (pinfunction "1_1") (pintype "passive"))
    )
    (net (code "148") (name "Net-(IC2-FB)") (class "Default")
      (node (ref "C16") (pin "2") (pinfunction "2_2") (pintype "passive"))
      (node (ref "IC2") (pin "4") (pinfunction "FB_4") (pintype "input"))
      (node (ref "R1") (pin "A") (pinfunction "A_A") (pintype "passive"))
      (node (ref "R1") (pin "S") (pinfunction "S_S") (pintype "passive"))
      (node (ref "R2") (pin "2") (pinfunction "2_2") (pintype "passive"))
    )
    (net (code "149") (name "Net-(IC2-OUT)") (class "Default")
      (node (ref "D3") (pin "C") (pinfunction "C_C") (pintype "passive"))
      (node (ref "IC2") (pin "2") (pinfunction "OUT_2") (pintype "output"))
      (node (ref "L1") (pin "1") (pinfunction "1_1") (pintype "passive"))
    )
    (net (code "150") (name "Net-(IC3-VI)") (class "Default")
      (node (ref "C5") (pin "+") (pinfunction "+_+") (pintype "passive"))
      (node (ref "D1") (pin "C") (pinfunction "C_C") (pintype "passive"))
      (node (ref "IC3") (pin "1") (pinfunction "VI_1") (pintype "input"))
    )
    (net (code "151") (name "Net-(IC4-FB)") (class "Default")
      (node (ref "C20") (pin "2") (pinfunction "2_2") (pintype "passive"))
      (node (ref "IC4") (pin "4") (pinfunction "FB_4") (pintype "input"))
      (node (ref "R10") (pin "A") (pinfunction "A_A") (pintype "passive"))
      (node (ref "R10") (pin "S") (pinfunction "S_S") (pintype "passive"))
      (node (ref "R11") (pin "2") (pinfunction "2_2") (pintype "passive"))
    )
    (net (code "152") (name "Net-(IC4-OUT)") (class "Default")
      (node (ref "D4") (pin "C") (pinfunction "C_C") (pintype "passive"))
      (node (ref "IC4") (pin "2") (pinfunction "OUT_2") (pintype "output"))
      (node (ref "L2") (pin "1") (pinfunction "1_1") (pintype "passive"))
    )
    (net (code "153") (name "Net-(IC5-FB)") (class "Default")
      (node (ref "C24") (pin "2") (pinfunction "2_2") (pintype "passive"))
      (node (ref "IC5") (pin "4") (pinfunction "FB_4") (pintype "input"))
      (node (ref "R13") (pin "A") (pinfunction "A_A") (pintype "passive"))
      (node (ref "R13") (pin "S") (pinfunction "S_S") (pintype "passive"))
      (node (ref "R14") (pin "2") (pinfunction "2_2") (pintype "passive"))
    )
    (net (code "154") (name "Net-(IC5-OUT)") (class "Default")
      (node (ref "D5") (pin "C") (pinfunction "C_C") (pintype "passive"))
      (node (ref "IC5") (pin "2") (pinfunction "OUT_2") (pintype "output"))
      (node (ref "L3") (pin "1") (pinfunction "1_1") (pintype "passive"))
    )
    (net (code "155") (name "Net-(LED1-1-DI)") (class "Default")
      (node (ref "LED1-1") (pin "4-DIN") (pinfunction "DI_4-DIN") (pintype "input"))
      (node (ref "R12") (pin "1") (pinfunction "1_1") (pintype "passive"))
    )
    (net (code "156") (name "Net-(LED1-1-DO)") (class "Default")
      (node (ref "LED1-1") (pin "2-DOUT") (pinfunction "DO_2-DOUT") (pintype "output"))
      (node (ref "LED1-2") (pin "4-DIN") (pinfunction "DI_4-DIN") (pintype "input"))
    )
    (net (code "157") (name "Net-(LED1-2-DO)") (class "Default")
      (node (ref "LED1-2") (pin "2-DOUT") (pinfunction "DO_2-DOUT") (pintype "output"))
      (node (ref "LED1-3") (pin "4-DIN") (pinfunction "DI_4-DIN") (pintype "input"))
    )
    (net (code "158") (name "Net-(LED1-3-DO)") (class "Default")
      (node (ref "LED1-3") (pin "2-DOUT") (pinfunction "DO_2-DOUT") (pintype "output"))
      (node (ref "LED1-4") (pin "4-DIN") (pinfunction "DI_4-DIN") (pintype "input"))
    )
    (net (code "159") (name "Net-(LED1-4-DO)") (class "Default")
      (node (ref "LED1-4") (pin "2-DOUT") (pinfunction "DO_2-DOUT") (pintype "output"))
      (node (ref "LED1-5") (pin "4-DIN") (pinfunction "DI_4-DIN") (pintype "input"))
    )
    (net (code "160") (name "Net-(LED1-5-DO)") (class "Default")
      (node (ref "LED1-5") (pin "2-DOUT") (pinfunction "DO_2-DOUT") (pintype "output"))
      (node (ref "LED1-6") (pin "4-DIN") (pinfunction "DI_4-DIN") (pintype "input"))
    )
    (net (code "161") (name "Net-(LED1-6-DO)") (class "Default")
      (node (ref "LED1-6") (pin "2-DOUT") (pinfunction "DO_2-DOUT") (pintype "output"))
      (node (ref "LED1-7") (pin "4-DIN") (pinfunction "DI_4-DIN") (pintype "input"))
    )
    (net (code "162") (name "Net-(LED1-7-DO)") (class "Default")
      (node (ref "LED1-7") (pin "2-DOUT") (pinfunction "DO_2-DOUT") (pintype "output"))
      (node (ref "LED1-8") (pin "4-DIN") (pinfunction "DI_4-DIN") (pintype "input"))
    )
    (net (code "163") (name "Net-(LED1-8-DO)") (class "Default")
      (node (ref "LED1-8") (pin "2-DOUT") (pinfunction "DO_2-DOUT") (pintype "output"))
      (node (ref "LED2-1") (pin "4-DIN") (pinfunction "DI_4-DIN") (pintype "input"))
    )
    (net (code "164") (name "Net-(LED1-PadA)") (class "Default")
      (node (ref "LED1") (pin "A") (pinfunction "A_A") (pintype "passive"))
      (node (ref "R4") (pin "1") (pinfunction "1_1") (pintype "passive"))
    )
    (net (code "165") (name "Net-(LED2-1-DO)") (class "Default")
      (node (ref "LED2-1") (pin "2-DOUT") (pinfunction "DO_2-DOUT") (pintype "output"))
      (node (ref "LED2-2") (pin "4-DIN") (pinfunction "DI_4-DIN") (pintype "input"))
    )
    (net (code "166") (name "Net-(LED2-2-DO)") (class "Default")
      (node (ref "LED2-2") (pin "2-DOUT") (pinfunction "DO_2-DOUT") (pintype "output"))
      (node (ref "LED2-3") (pin "4-DIN") (pinfunction "DI_4-DIN") (pintype "input"))
    )
    (net (code "167") (name "Net-(LED2-3-DO)") (class "Default")
      (node (ref "LED2-3") (pin "2-DOUT") (pinfunction "DO_2-DOUT") (pintype "output"))
      (node (ref "LED2-4") (pin "4-DIN") (pinfunction "DI_4-DIN") (pintype "input"))
    )
    (net (code "168") (name "Net-(LED2-4-DO)") (class "Default")
      (node (ref "LED2-4") (pin "2-DOUT") (pinfunction "DO_2-DOUT") (pintype "output"))
      (node (ref "LED2-5") (pin "4-DIN") (pinfunction "DI_4-DIN") (pintype "input"))
    )
    (net (code "169") (name "Net-(LED2-5-DO)") (class "Default")
      (node (ref "LED2-5") (pin "2-DOUT") (pinfunction "DO_2-DOUT") (pintype "output"))
      (node (ref "LED2-6") (pin "4-DIN") (pinfunction "DI_4-DIN") (pintype "input"))
    )
    (net (code "170") (name "Net-(LED2-6-DO)") (class "Default")
      (node (ref "LED2-6") (pin "2-DOUT") (pinfunction "DO_2-DOUT") (pintype "output"))
      (node (ref "LED2-7") (pin "4-DIN") (pinfunction "DI_4-DIN") (pintype "input"))
    )
    (net (code "171") (name "Net-(LED2-7-DO)") (class "Default")
      (node (ref "LED2-7") (pin "2-DOUT") (pinfunction "DO_2-DOUT") (pintype "output"))
      (node (ref "LED2-8") (pin "4-DIN") (pinfunction "DI_4-DIN") (pintype "input"))
    )
    (net (code "172") (name "Net-(LED2-8-DO)") (class "Default")
      (node (ref "LED2-8") (pin "2-DOUT") (pinfunction "DO_2-DOUT") (pintype "output"))
      (node (ref "LED3-1") (pin "4-DIN") (pinfunction "DI_4-DIN") (pintype "input"))
    )
    (net (code "173") (name "Net-(LED2-PadA)") (class "Default")
      (node (ref "LED2") (pin "A") (pinfunction "A_A") (pintype "passive"))
      (node (ref "R5") (pin "1") (pinfunction "1_1") (pintype "passive"))
    )
    (net (code "174") (name "Net-(LED3-1-DO)") (class "Default")
      (node (ref "LED3-1") (pin "2-DOUT") (pinfunction "DO_2-DOUT") (pintype "output"))
      (node (ref "LED3-2") (pin "4-DIN") (pinfunction "DI_4-DIN") (pintype "input"))
    )
    (net (code "175") (name "Net-(LED3-2-DO)") (class "Default")
      (node (ref "LED3-2") (pin "2-DOUT") (pinfunction "DO_2-DOUT") (pintype "output"))
      (node (ref "LED3-3") (pin "4-DIN") (pinfunction "DI_4-DIN") (pintype "input"))
    )
    (net (code "176") (name "Net-(LED3-3-DO)") (class "Default")
      (node (ref "LED3-3") (pin "2-DOUT") (pinfunction "DO_2-DOUT") (pintype "output"))
      (node (ref "LED3-4") (pin "4-DIN") (pinfunction "DI_4-DIN") (pintype "input"))
    )
    (net (code "177") (name "Net-(LED3-4-DO)") (class "Default")
      (node (ref "LED3-4") (pin "2-DOUT") (pinfunction "DO_2-DOUT") (pintype "output"))
      (node (ref "LED3-5") (pin "4-DIN") (pinfunction "DI_4-DIN") (pintype "input"))
    )
    (net (code "178") (name "Net-(LED3-5-DO)") (class "Default")
      (node (ref "LED3-5") (pin "2-DOUT") (pinfunction "DO_2-DOUT") (pintype "output"))
      (node (ref "LED3-6") (pin "4-DIN") (pinfunction "DI_4-DIN") (pintype "input"))
    )
    (net (code "179") (name "Net-(LED3-6-DO)") (class "Default")
      (node (ref "LED3-6") (pin "2-DOUT") (pinfunction "DO_2-DOUT") (pintype "output"))
      (node (ref "LED3-7") (pin "4-DIN") (pinfunction "DI_4-DIN") (pintype "input"))
    )
    (net (code "180") (name "Net-(LED3-7-DO)") (class "Default")
      (node (ref "LED3-7") (pin "2-DOUT") (pinfunction "DO_2-DOUT") (pintype "output"))
      (node (ref "LED3-8") (pin "4-DIN") (pinfunction "DI_4-DIN") (pintype "input"))
    )
    (net (code "181") (name "Net-(LED3-8-DO)") (class "Default")
      (node (ref "LED3-8") (pin "2-DOUT") (pinfunction "DO_2-DOUT") (pintype "output"))
      (node (ref "LED4-1") (pin "4-DIN") (pinfunction "DI_4-DIN") (pintype "input"))
    )
    (net (code "182") (name "Net-(LED3-PadC)") (class "Default")
      (node (ref "LED3") (pin "C") (pinfunction "C_C") (pintype "passive"))
      (node (ref "R8") (pin "1") (pinfunction "1_1") (pintype "passive"))
    )
    (net (code "183") (name "Net-(LED4-1-DO)") (class "Default")
      (node (ref "LED4-1") (pin "2-DOUT") (pinfunction "DO_2-DOUT") (pintype "output"))
      (node (ref "LED4-2") (pin "4-DIN") (pinfunction "DI_4-DIN") (pintype "input"))
    )
    (net (code "184") (name "Net-(LED4-2-DO)") (class "Default")
      (node (ref "LED4-2") (pin "2-DOUT") (pinfunction "DO_2-DOUT") (pintype "output"))
      (node (ref "LED4-3") (pin "4-DIN") (pinfunction "DI_4-DIN") (pintype "input"))
    )
    (net (code "185") (name "Net-(LED4-3-DO)") (class "Default")
      (node (ref "LED4-3") (pin "2-DOUT") (pinfunction "DO_2-DOUT") (pintype "output"))
      (node (ref "LED4-4") (pin "4-DIN") (pinfunction "DI_4-DIN") (pintype "input"))
    )
    (net (code "186") (name "Net-(LED4-4-DO)") (class "Default")
      (node (ref "LED4-4") (pin "2-DOUT") (pinfunction "DO_2-DOUT") (pintype "output"))
      (node (ref "LED4-5") (pin "4-DIN") (pinfunction "DI_4-DIN") (pintype "input"))
    )
    (net (code "187") (name "Net-(LED4-5-DO)") (class "Default")
      (node (ref "LED4-5") (pin "2-DOUT") (pinfunction "DO_2-DOUT") (pintype "output"))
      (node (ref "LED4-6") (pin "4-DIN") (pinfunction "DI_4-DIN") (pintype "input"))
    )
    (net (code "188") (name "Net-(LED4-6-DO)") (class "Default")
      (node (ref "LED4-6") (pin "2-DOUT") (pinfunction "DO_2-DOUT") (pintype "output"))
      (node (ref "LED4-7") (pin "4-DIN") (pinfunction "DI_4-DIN") (pintype "input"))
    )
    (net (code "189") (name "Net-(LED4-7-DO)") (class "Default")
      (node (ref "LED4-7") (pin "2-DOUT") (pinfunction "DO_2-DOUT") (pintype "output"))
      (node (ref "LED4-8") (pin "4-DIN") (pinfunction "DI_4-DIN") (pintype "input"))
    )
    (net (code "190") (name "Net-(LED4-8-DO)") (class "Default")
      (node (ref "LED4-8") (pin "2-DOUT") (pinfunction "DO_2-DOUT") (pintype "output"))
      (node (ref "LED5-1") (pin "4-DIN") (pinfunction "DI_4-DIN") (pintype "input"))
    )
    (net (code "191") (name "Net-(LED4-PadC)") (class "Default")
      (node (ref "LED4") (pin "C") (pinfunction "C_C") (pintype "passive"))
      (node (ref "R9") (pin "1") (pinfunction "1_1") (pintype "passive"))
    )
    (net (code "192") (name "Net-(LED5-1-DO)") (class "Default")
      (node (ref "LED5-1") (pin "2-DOUT") (pinfunction "DO_2-DOUT") (pintype "output"))
      (node (ref "LED5-2") (pin "4-DIN") (pinfunction "DI_4-DIN") (pintype "input"))
    )
    (net (code "193") (name "Net-(LED5-2-DO)") (class "Default")
      (node (ref "LED5-2") (pin "2-DOUT") (pinfunction "DO_2-DOUT") (pintype "output"))
      (node (ref "LED5-3") (pin "4-DIN") (pinfunction "DI_4-DIN") (pintype "input"))
    )
    (net (code "194") (name "Net-(LED5-3-DO)") (class "Default")
      (node (ref "LED5-3") (pin "2-DOUT") (pinfunction "DO_2-DOUT") (pintype "output"))
      (node (ref "LED5-4") (pin "4-DIN") (pinfunction "DI_4-DIN") (pintype "input"))
    )
    (net (code "195") (name "Net-(LED5-4-DO)") (class "Default")
      (node (ref "LED5-4") (pin "2-DOUT") (pinfunction "DO_2-DOUT") (pintype "output"))
      (node (ref "LED5-5") (pin "4-DIN") (pinfunction "DI_4-DIN") (pintype "input"))
    )
    (net (code "196") (name "Net-(LED5-5-DO)") (class "Default")
      (node (ref "LED5-5") (pin "2-DOUT") (pinfunction "DO_2-DOUT") (pintype "output"))
      (node (ref "LED5-6") (pin "4-DIN") (pinfunction "DI_4-DIN") (pintype "input"))
    )
    (net (code "197") (name "Net-(LED5-6-DO)") (class "Default")
      (node (ref "LED5-6") (pin "2-DOUT") (pinfunction "DO_2-DOUT") (pintype "output"))
      (node (ref "LED5-7") (pin "4-DIN") (pinfunction "DI_4-DIN") (pintype "input"))
    )
    (net (code "198") (name "Net-(LED5-7-DO)") (class "Default")
      (node (ref "LED5-7") (pin "2-DOUT") (pinfunction "DO_2-DOUT") (pintype "output"))
      (node (ref "LED5-8") (pin "4-DIN") (pinfunction "DI_4-DIN") (pintype "input"))
    )
    (net (code "199") (name "Net-(LED5-8-DO)") (class "Default")
      (node (ref "LED5-8") (pin "2-DOUT") (pinfunction "DO_2-DOUT") (pintype "output"))
      (node (ref "LED6-1") (pin "4-DIN") (pinfunction "DI_4-DIN") (pintype "input"))
    )
    (net (code "200") (name "Net-(LED6-1-DO)") (class "Default")
      (node (ref "LED6-1") (pin "2-DOUT") (pinfunction "DO_2-DOUT") (pintype "output"))
      (node (ref "LED6-2") (pin "4-DIN") (pinfunction "DI_4-DIN") (pintype "input"))
    )
    (net (code "201") (name "Net-(LED6-2-DO)") (class "Default")
      (node (ref "LED6-2") (pin "2-DOUT") (pinfunction "DO_2-DOUT") (pintype "output"))
      (node (ref "LED6-3") (pin "4-DIN") (pinfunction "DI_4-DIN") (pintype "input"))
    )
    (net (code "202") (name "Net-(LED6-3-DO)") (class "Default")
      (node (ref "LED6-3") (pin "2-DOUT") (pinfunction "DO_2-DOUT") (pintype "output"))
      (node (ref "LED6-4") (pin "4-DIN") (pinfunction "DI_4-DIN") (pintype "input"))
    )
    (net (code "203") (name "Net-(LED6-4-DO)") (class "Default")
      (node (ref "LED6-4") (pin "2-DOUT") (pinfunction "DO_2-DOUT") (pintype "output"))
      (node (ref "LED6-5") (pin "4-DIN") (pinfunction "DI_4-DIN") (pintype "input"))
    )
    (net (code "204") (name "Net-(LED6-5-DO)") (class "Default")
      (node (ref "LED6-5") (pin "2-DOUT") (pinfunction "DO_2-DOUT") (pintype "output"))
      (node (ref "LED6-6") (pin "4-DIN") (pinfunction "DI_4-DIN") (pintype "input"))
    )
    (net (code "205") (name "Net-(LED6-6-DO)") (class "Default")
      (node (ref "LED6-6") (pin "2-DOUT") (pinfunction "DO_2-DOUT") (pintype "output"))
      (node (ref "LED6-7") (pin "4-DIN") (pinfunction "DI_4-DIN") (pintype "input"))
    )
    (net (code "206") (name "Net-(LED6-7-DO)") (class "Default")
      (node (ref "LED6-7") (pin "2-DOUT") (pinfunction "DO_2-DOUT") (pintype "output"))
      (node (ref "LED6-8") (pin "4-DIN") (pinfunction "DI_4-DIN") (pintype "input"))
    )
    (net (code "207") (name "Net-(LED6-8-DO)") (class "Default")
      (node (ref "LED6-8") (pin "2-DOUT") (pinfunction "DO_2-DOUT") (pintype "output"))
      (node (ref "LED7-1") (pin "4-DIN") (pinfunction "DI_4-DIN") (pintype "input"))
    )
    (net (code "208") (name "Net-(LED7-1-DO)") (class "Default")
      (node (ref "LED7-1") (pin "2-DOUT") (pinfunction "DO_2-DOUT") (pintype "output"))
      (node (ref "LED7-2") (pin "4-DIN") (pinfunction "DI_4-DIN") (pintype "input"))
    )
    (net (code "209") (name "Net-(LED7-2-DO)") (class "Default")
      (node (ref "LED7-2") (pin "2-DOUT") (pinfunction "DO_2-DOUT") (pintype "output"))
      (node (ref "LED7-3") (pin "4-DIN") (pinfunction "DI_4-DIN") (pintype "input"))
    )
    (net (code "210") (name "Net-(LED7-3-DO)") (class "Default")
      (node (ref "LED7-3") (pin "2-DOUT") (pinfunction "DO_2-DOUT") (pintype "output"))
      (node (ref "LED7-4") (pin "4-DIN") (pinfunction "DI_4-DIN") (pintype "input"))
    )
    (net (code "211") (name "Net-(LED7-4-DO)") (class "Default")
      (node (ref "LED7-4") (pin "2-DOUT") (pinfunction "DO_2-DOUT") (pintype "output"))
      (node (ref "LED7-5") (pin "4-DIN") (pinfunction "DI_4-DIN") (pintype "input"))
    )
    (net (code "212") (name "Net-(LED7-5-DO)") (class "Default")
      (node (ref "LED7-5") (pin "2-DOUT") (pinfunction "DO_2-DOUT") (pintype "output"))
      (node (ref "LED7-6") (pin "4-DIN") (pinfunction "DI_4-DIN") (pintype "input"))
    )
    (net (code "213") (name "Net-(LED7-6-DO)") (class "Default")
      (node (ref "LED7-6") (pin "2-DOUT") (pinfunction "DO_2-DOUT") (pintype "output"))
      (node (ref "LED7-7") (pin "4-DIN") (pinfunction "DI_4-DIN") (pintype "input"))
    )
    (net (code "214") (name "Net-(LED7-7-DO)") (class "Default")
      (node (ref "LED7-7") (pin "2-DOUT") (pinfunction "DO_2-DOUT") (pintype "output"))
      (node (ref "LED7-8") (pin "4-DIN") (pinfunction "DI_4-DIN") (pintype "input"))
    )
    (net (code "215") (name "Net-(LED7-8-DO)") (class "Default")
      (node (ref "LED7-8") (pin "2-DOUT") (pinfunction "DO_2-DOUT") (pintype "output"))
      (node (ref "LED8-1") (pin "4-DIN") (pinfunction "DI_4-DIN") (pintype "input"))
    )
    (net (code "216") (name "Net-(LED8-1-DO)") (class "Default")
      (node (ref "LED8-1") (pin "2-DOUT") (pinfunction "DO_2-DOUT") (pintype "output"))
      (node (ref "LED8-2") (pin "4-DIN") (pinfunction "DI_4-DIN") (pintype "input"))
    )
    (net (code "217") (name "Net-(LED8-2-DO)") (class "Default")
      (node (ref "LED8-2") (pin "2-DOUT") (pinfunction "DO_2-DOUT") (pintype "output"))
      (node (ref "LED8-3") (pin "4-DIN") (pinfunction "DI_4-DIN") (pintype "input"))
    )
    (net (code "218") (name "Net-(LED8-3-DO)") (class "Default")
      (node (ref "LED8-3") (pin "2-DOUT") (pinfunction "DO_2-DOUT") (pintype "output"))
      (node (ref "LED8-4") (pin "4-DIN") (pinfunction "DI_4-DIN") (pintype "input"))
    )
    (net (code "219") (name "Net-(LED8-4-DO)") (class "Default")
      (node (ref "LED8-4") (pin "2-DOUT") (pinfunction "DO_2-DOUT") (pintype "output"))
      (node (ref "LED8-5") (pin "4-DIN") (pinfunction "DI_4-DIN") (pintype "input"))
    )
    (net (code "220") (name "Net-(LED8-5-DO)") (class "Default")
      (node (ref "LED8-5") (pin "2-DOUT") (pinfunction "DO_2-DOUT") (pintype "output"))
      (node (ref "LED8-6") (pin "4-DIN") (pinfunction "DI_4-DIN") (pintype "input"))
    )
    (net (code "221") (name "Net-(LED8-6-DO)") (class "Default")
      (node (ref "LED8-6") (pin "2-DOUT") (pinfunction "DO_2-DOUT") (pintype "output"))
      (node (ref "LED8-7") (pin "4-DIN") (pinfunction "DI_4-DIN") (pintype "input"))
    )
    (net (code "222") (name "Net-(LED8-7-DO)") (class "Default")
      (node (ref "LED8-7") (pin "2-DOUT") (pinfunction "DO_2-DOUT") (pintype "output"))
      (node (ref "LED8-8") (pin "4-DIN") (pinfunction "DI_4-DIN") (pintype "input"))
    )
    (net (code "223") (name "Net-(R15-Pad1)") (class "Default")
      (node (ref "R15") (pin "1") (pinfunction "1_1") (pintype "passive"))
      (node (ref "R16") (pin "1") (pinfunction "1_1") (pintype "passive"))
      (node (ref "U$50") (pin "3") (pinfunction "3_3") (pintype "passive"))
    )
    (net (code "224") (name "Net-(STEPDRV1-1A)") (class "Default")
      (node (ref "J1") (pin "3") (pinfunction "3_3") (pintype "passive"))
      (node (ref "STEPDRV1") (pin "12") (pinfunction "1A_12") (pintype "output"))
    )
    (net (code "225") (name "Net-(STEPDRV1-1B)") (class "Default")
      (node (ref "J1") (pin "4") (pinfunction "4_4") (pintype "passive"))
      (node (ref "STEPDRV1") (pin "11") (pinfunction "1B_11") (pintype "output"))
    )
    (net (code "226") (name "Net-(STEPDRV1-2A)") (class "Default")
      (node (ref "J1") (pin "2") (pinfunction "2_2") (pintype "passive"))
      (node (ref "STEPDRV1") (pin "13") (pinfunction "2A_13") (pintype "output"))
    )
    (net (code "227") (name "Net-(STEPDRV1-2B)") (class "Default")
      (node (ref "J1") (pin "1") (pinfunction "1_1") (pintype "passive"))
      (node (ref "STEPDRV1") (pin "14") (pinfunction "2B_14") (pintype "output"))
    )
    (net (code "228") (name "Net-(STEPDRV1-~{RESET})") (class "Default")
      (node (ref "STEPDRV1") (pin "5") (pinfunction "~{RESET}_5") (pintype "input"))
      (node (ref "STEPDRV1") (pin "6") (pinfunction "~{SLEEP}_6") (pintype "input"))
    )
    (net (code "229") (name "Net-(STEPDRV2-1A)") (class "Default")
      (node (ref "J2") (pin "3") (pinfunction "3_3") (pintype "passive"))
      (node (ref "STEPDRV2") (pin "12") (pinfunction "1A_12") (pintype "output"))
    )
    (net (code "230") (name "Net-(STEPDRV2-1B)") (class "Default")
      (node (ref "J2") (pin "4") (pinfunction "4_4") (pintype "passive"))
      (node (ref "STEPDRV2") (pin "11") (pinfunction "1B_11") (pintype "output"))
    )
    (net (code "231") (name "Net-(STEPDRV2-2A)") (class "Default")
      (node (ref "J2") (pin "2") (pinfunction "2_2") (pintype "passive"))
      (node (ref "STEPDRV2") (pin "13") (pinfunction "2A_13") (pintype "output"))
    )
    (net (code "232") (name "Net-(STEPDRV2-2B)") (class "Default")
      (node (ref "J2") (pin "1") (pinfunction "1_1") (pintype "passive"))
      (node (ref "STEPDRV2") (pin "14") (pinfunction "2B_14") (pintype "output"))
    )
    (net (code "233") (name "Net-(STEPDRV2-~{RESET})") (class "Default")
      (node (ref "STEPDRV2") (pin "5") (pinfunction "~{RESET}_5") (pintype "input"))
      (node (ref "STEPDRV2") (pin "6") (pinfunction "~{SLEEP}_6") (pintype "input"))
    )
    (net (code "234") (name "Net-(U1-RXLED)") (class "Default")
      (node (ref "R9") (pin "2") (pinfunction "2_2") (pintype "passive"))
      (node (ref "U1") (pin "22") (pinfunction "RXLED_22") (pintype "bidirectional"))
    )
    (net (code "235") (name "Net-(U1-TXLED)") (class "Default")
      (node (ref "R8") (pin "2") (pinfunction "2_2") (pintype "passive"))
      (node (ref "U1") (pin "23") (pinfunction "TXLED_23") (pintype "bidirectional"))
    )
    (net (code "236") (name "Net-(U1-USB+)") (class "Default")
      (node (ref "J3") (pin "D+") (pinfunction "D+_D+") (pintype "bidirectional"))
      (node (ref "U1") (pin "15") (pinfunction "USB+_15") (pintype "bidirectional"))
    )
    (net (code "237") (name "Net-(U1-USB-)") (class "Default")
      (node (ref "J3") (pin "D-") (pinfunction "D-_D-") (pintype "bidirectional"))
      (node (ref "U1") (pin "16") (pinfunction "USB-_16") (pintype "bidirectional"))
    )
    (net (code "238") (name "RESET") (class "Default")
      (node (ref "C4") (pin "1") (pinfunction "P$1_1") (pintype "passive"))
      (node (ref "C7") (pin "2") (pinfunction "P$2_2") (pintype "passive"))
      (node (ref "IC1") (pin "30") (pinfunction "RESET_30") (pintype "input"))
      (node (ref "ICSP") (pin "5") (pinfunction "5_5") (pintype "bidirectional"))
      (node (ref "R3") (pin "1") (pinfunction "1_1") (pintype "passive"))
      (node (ref "S1") (pin "3") (pinfunction "3_3") (pintype "passive"))
      (node (ref "S1") (pin "4") (pinfunction "4_4") (pintype "passive"))
    )
    (net (code "239") (name "VIN") (class "Default")
      (node (ref "C13") (pin "+") (pinfunction "+_+") (pintype "passive"))
      (node (ref "C15") (pin "2") (pinfunction "2_2") (pintype "passive"))
      (node (ref "C17") (pin "+") (pinfunction "+_+") (pintype "passive"))
      (node (ref "C19") (pin "2") (pinfunction "2_2") (pintype "passive"))
      (node (ref "C21") (pin "+") (pinfunction "+_+") (pintype "passive"))
      (node (ref "C23") (pin "2") (pinfunction "2_2") (pintype "passive"))
      (node (ref "D1") (pin "A") (pinfunction "A_A") (pintype "passive"))
      (node (ref "F1") (pin "2A") (pinfunction "2A_2A") (pintype "passive"))
      (node (ref "IC2") (pin "1") (pinfunction "VIN_1") (pintype "input"))
      (node (ref "IC4") (pin "1") (pinfunction "VIN_1") (pintype "input"))
      (node (ref "IC5") (pin "1") (pinfunction "VIN_1") (pintype "input"))
    )
    (net (code "240") (name "VUSB") (class "Default")
      (node (ref "C10") (pin "2") (pinfunction "P$2_2") (pintype "passive"))
      (node (ref "C31") (pin "1") (pinfunction "1_1") (pintype "passive"))
      (node (ref "D2") (pin "A") (pinfunction "A_A") (pintype "passive"))
      (node (ref "J3") (pin "VBUS") (pinfunction "VBUS_VBUS") (pintype "power_in"))
    )
    (net (code "241") (name "unconnected-(F1-Pad1B)") (class "Default")
      (node (ref "F1") (pin "1B") (pinfunction "1B_1B") (pintype "passive"))
    )
    (net (code "242") (name "unconnected-(F1-Pad2B)") (class "Default")
      (node (ref "F1") (pin "2B") (pinfunction "2B_2B") (pintype "passive"))
    )
    (net (code "243") (name "unconnected-(IC1-(CLKO{slash}ICP3{slash}INT7)PE7-Pad9)") (class "Default")
      (node (ref "IC1") (pin "9") (pinfunction "(CLKO/ICP3/INT7)PE7_9") (pintype "bidirectional"))
    )
    (net (code "244") (name "unconnected-(IC1-(ICP1)PD4-Pad47)") (class "Default")
      (node (ref "IC1") (pin "47") (pinfunction "(ICP1)PD4_47") (pintype "bidirectional"))
    )
    (net (code "245") (name "unconnected-(IC1-(T1)PD6-Pad49)") (class "Default")
      (node (ref "IC1") (pin "49") (pinfunction "(T1)PD6_49") (pintype "bidirectional"))
    )
    (net (code "246") (name "unconnected-(IC1-(T3{slash}INT6)PE6-Pad8)") (class "Default")
      (node (ref "IC1") (pin "8") (pinfunction "(T3/INT6)PE6_8") (pintype "bidirectional"))
    )
    (net (code "247") (name "unconnected-(IC1-(TOSC1)PG4-Pad29)") (class "Default")
      (node (ref "IC1") (pin "29") (pinfunction "(TOSC1)PG4_29") (pintype "bidirectional"))
    )
    (net (code "248") (name "unconnected-(IC1-(TOSC2)PG3-Pad28)") (class "Default")
      (node (ref "IC1") (pin "28") (pinfunction "(TOSC2)PG3_28") (pintype "bidirectional"))
    )
    (net (code "249") (name "unconnected-(IC1-(XCK0{slash}AIN0)PE2-Pad4)") (class "Default")
      (node (ref "IC1") (pin "4") (pinfunction "(XCK0/AIN0)PE2_4") (pintype "bidirectional"))
    )
    (net (code "250") (name "unconnected-(IC1-(XCK1)PD5-Pad48)") (class "Default")
      (node (ref "IC1") (pin "48") (pinfunction "(XCK1)PD5_48") (pintype "bidirectional"))
    )
    (net (code "251") (name "unconnected-(IC1-PH2(XCK2)-Pad14)") (class "Default")
      (node (ref "IC1") (pin "14") (pinfunction "PH2(XCK2)_14") (pintype "bidirectional"))
    )
    (net (code "252") (name "unconnected-(IC1-PH7(T4)-Pad27)") (class "Default")
      (node (ref "IC1") (pin "27") (pinfunction "PH7(T4)_27") (pintype "bidirectional"))
    )
    (net (code "253") (name "unconnected-(IC1-PJ2(XCK3{slash}PCINT11)-Pad65)") (class "Default")
      (node (ref "IC1") (pin "65") (pinfunction "PJ2(XCK3/PCINT11)_65") (pintype "bidirectional"))
    )
    (net (code "254") (name "unconnected-(IC1-PJ3(PCINT12)-Pad66)") (class "Default")
      (node (ref "IC1") (pin "66") (pinfunction "PJ3(PCINT12)_66") (pintype "bidirectional"))
    )
    (net (code "255") (name "unconnected-(IC1-PJ4(PCINT13)-Pad67)") (class "Default")
      (node (ref "IC1") (pin "67") (pinfunction "PJ4(PCINT13)_67") (pintype "bidirectional"))
    )
    (net (code "256") (name "unconnected-(IC1-PJ5(PCINT14)-Pad68)") (class "Default")
      (node (ref "IC1") (pin "68") (pinfunction "PJ5(PCINT14)_68") (pintype "bidirectional"))
    )
    (net (code "257") (name "unconnected-(IC1-PJ6(PCINT15)-Pad69)") (class "Default")
      (node (ref "IC1") (pin "69") (pinfunction "PJ6(PCINT15)_69") (pintype "bidirectional"))
    )
    (net (code "258") (name "unconnected-(IC1-PJ7-Pad79)") (class "Default")
      (node (ref "IC1") (pin "79") (pinfunction "PJ7_79") (pintype "bidirectional"))
    )
    (net (code "259") (name "unconnected-(IC6-INTA-Pad16)") (class "Default")
      (node (ref "IC6") (pin "16") (pinfunction "INTA_16") (pintype "output"))
    )
    (net (code "260") (name "unconnected-(IC6-INTB-Pad15)") (class "Default")
      (node (ref "IC6") (pin "15") (pinfunction "INTB_15") (pintype "output"))
    )
    (net (code "261") (name "unconnected-(IC7-INTA-Pad16)") (class "Default")
      (node (ref "IC7") (pin "16") (pinfunction "INTA_16") (pintype "output"))
    )
    (net (code "262") (name "unconnected-(IC7-INTB-Pad15)") (class "Default")
      (node (ref "IC7") (pin "15") (pinfunction "INTB_15") (pintype "output"))
    )
    (net (code "263") (name "unconnected-(IC8-INTA-Pad16)") (class "Default")
      (node (ref "IC8") (pin "16") (pinfunction "INTA_16") (pintype "output"))
    )
    (net (code "264") (name "unconnected-(IC8-INTB-Pad15)") (class "Default")
      (node (ref "IC8") (pin "15") (pinfunction "INTB_15") (pintype "output"))
    )
    (net (code "265") (name "unconnected-(IC9-INTA-Pad16)") (class "Default")
      (node (ref "IC9") (pin "16") (pinfunction "INTA_16") (pintype "output"))
    )
    (net (code "266") (name "unconnected-(IC9-INTB-Pad15)") (class "Default")
      (node (ref "IC9") (pin "15") (pinfunction "INTB_15") (pintype "output"))
    )
    (net (code "267") (name "unconnected-(LED8-8-DO-Pad2-DOUT)") (class "Default")
      (node (ref "LED8-8") (pin "2-DOUT") (pinfunction "DO_2-DOUT") (pintype "output"))
    )
    (net (code "268") (name "unconnected-(STEPDRV1-MS1-Pad2)") (class "Default")
      (node (ref "STEPDRV1") (pin "2") (pinfunction "MS1_2") (pintype "input"))
    )
    (net (code "269") (name "unconnected-(STEPDRV1-MS2-Pad3)") (class "Default")
      (node (ref "STEPDRV1") (pin "3") (pinfunction "MS2_3") (pintype "input"))
    )
    (net (code "270") (name "unconnected-(STEPDRV1-MS3-Pad4)") (class "Default")
      (node (ref "STEPDRV1") (pin "4") (pinfunction "MS3_4") (pintype "input"))
    )
    (net (code "271") (name "unconnected-(STEPDRV2-MS1-Pad2)") (class "Default")
      (node (ref "STEPDRV2") (pin "2") (pinfunction "MS1_2") (pintype "input"))
    )
    (net (code "272") (name "unconnected-(STEPDRV2-MS2-Pad3)") (class "Default")
      (node (ref "STEPDRV2") (pin "3") (pinfunction "MS2_3") (pintype "input"))
    )
    (net (code "273") (name "unconnected-(STEPDRV2-MS3-Pad4)") (class "Default")
      (node (ref "STEPDRV2") (pin "4") (pinfunction "MS3_4") (pintype "input"))
    )
    (net (code "274") (name "unconnected-(U1-CTS-Pad11)") (class "Default")
      (node (ref "U1") (pin "11") (pinfunction "CTS_11") (pintype "bidirectional"))
    )
    (net (code "275") (name "unconnected-(U1-RTS-Pad3)") (class "Default")
      (node (ref "U1") (pin "3") (pinfunction "RTS_3") (pintype "bidirectional"))
    )
    (net (code "276") (name "unconnected-(U1-TEST-Pad26)") (class "Default")
      (node (ref "U1") (pin "26") (pinfunction "TEST_26") (pintype "input"))
    )
  )
)
